# SCH_Nucleo__V5_2022-11-29.net
KiCad netlist of a schematic drawn in EasyEDA
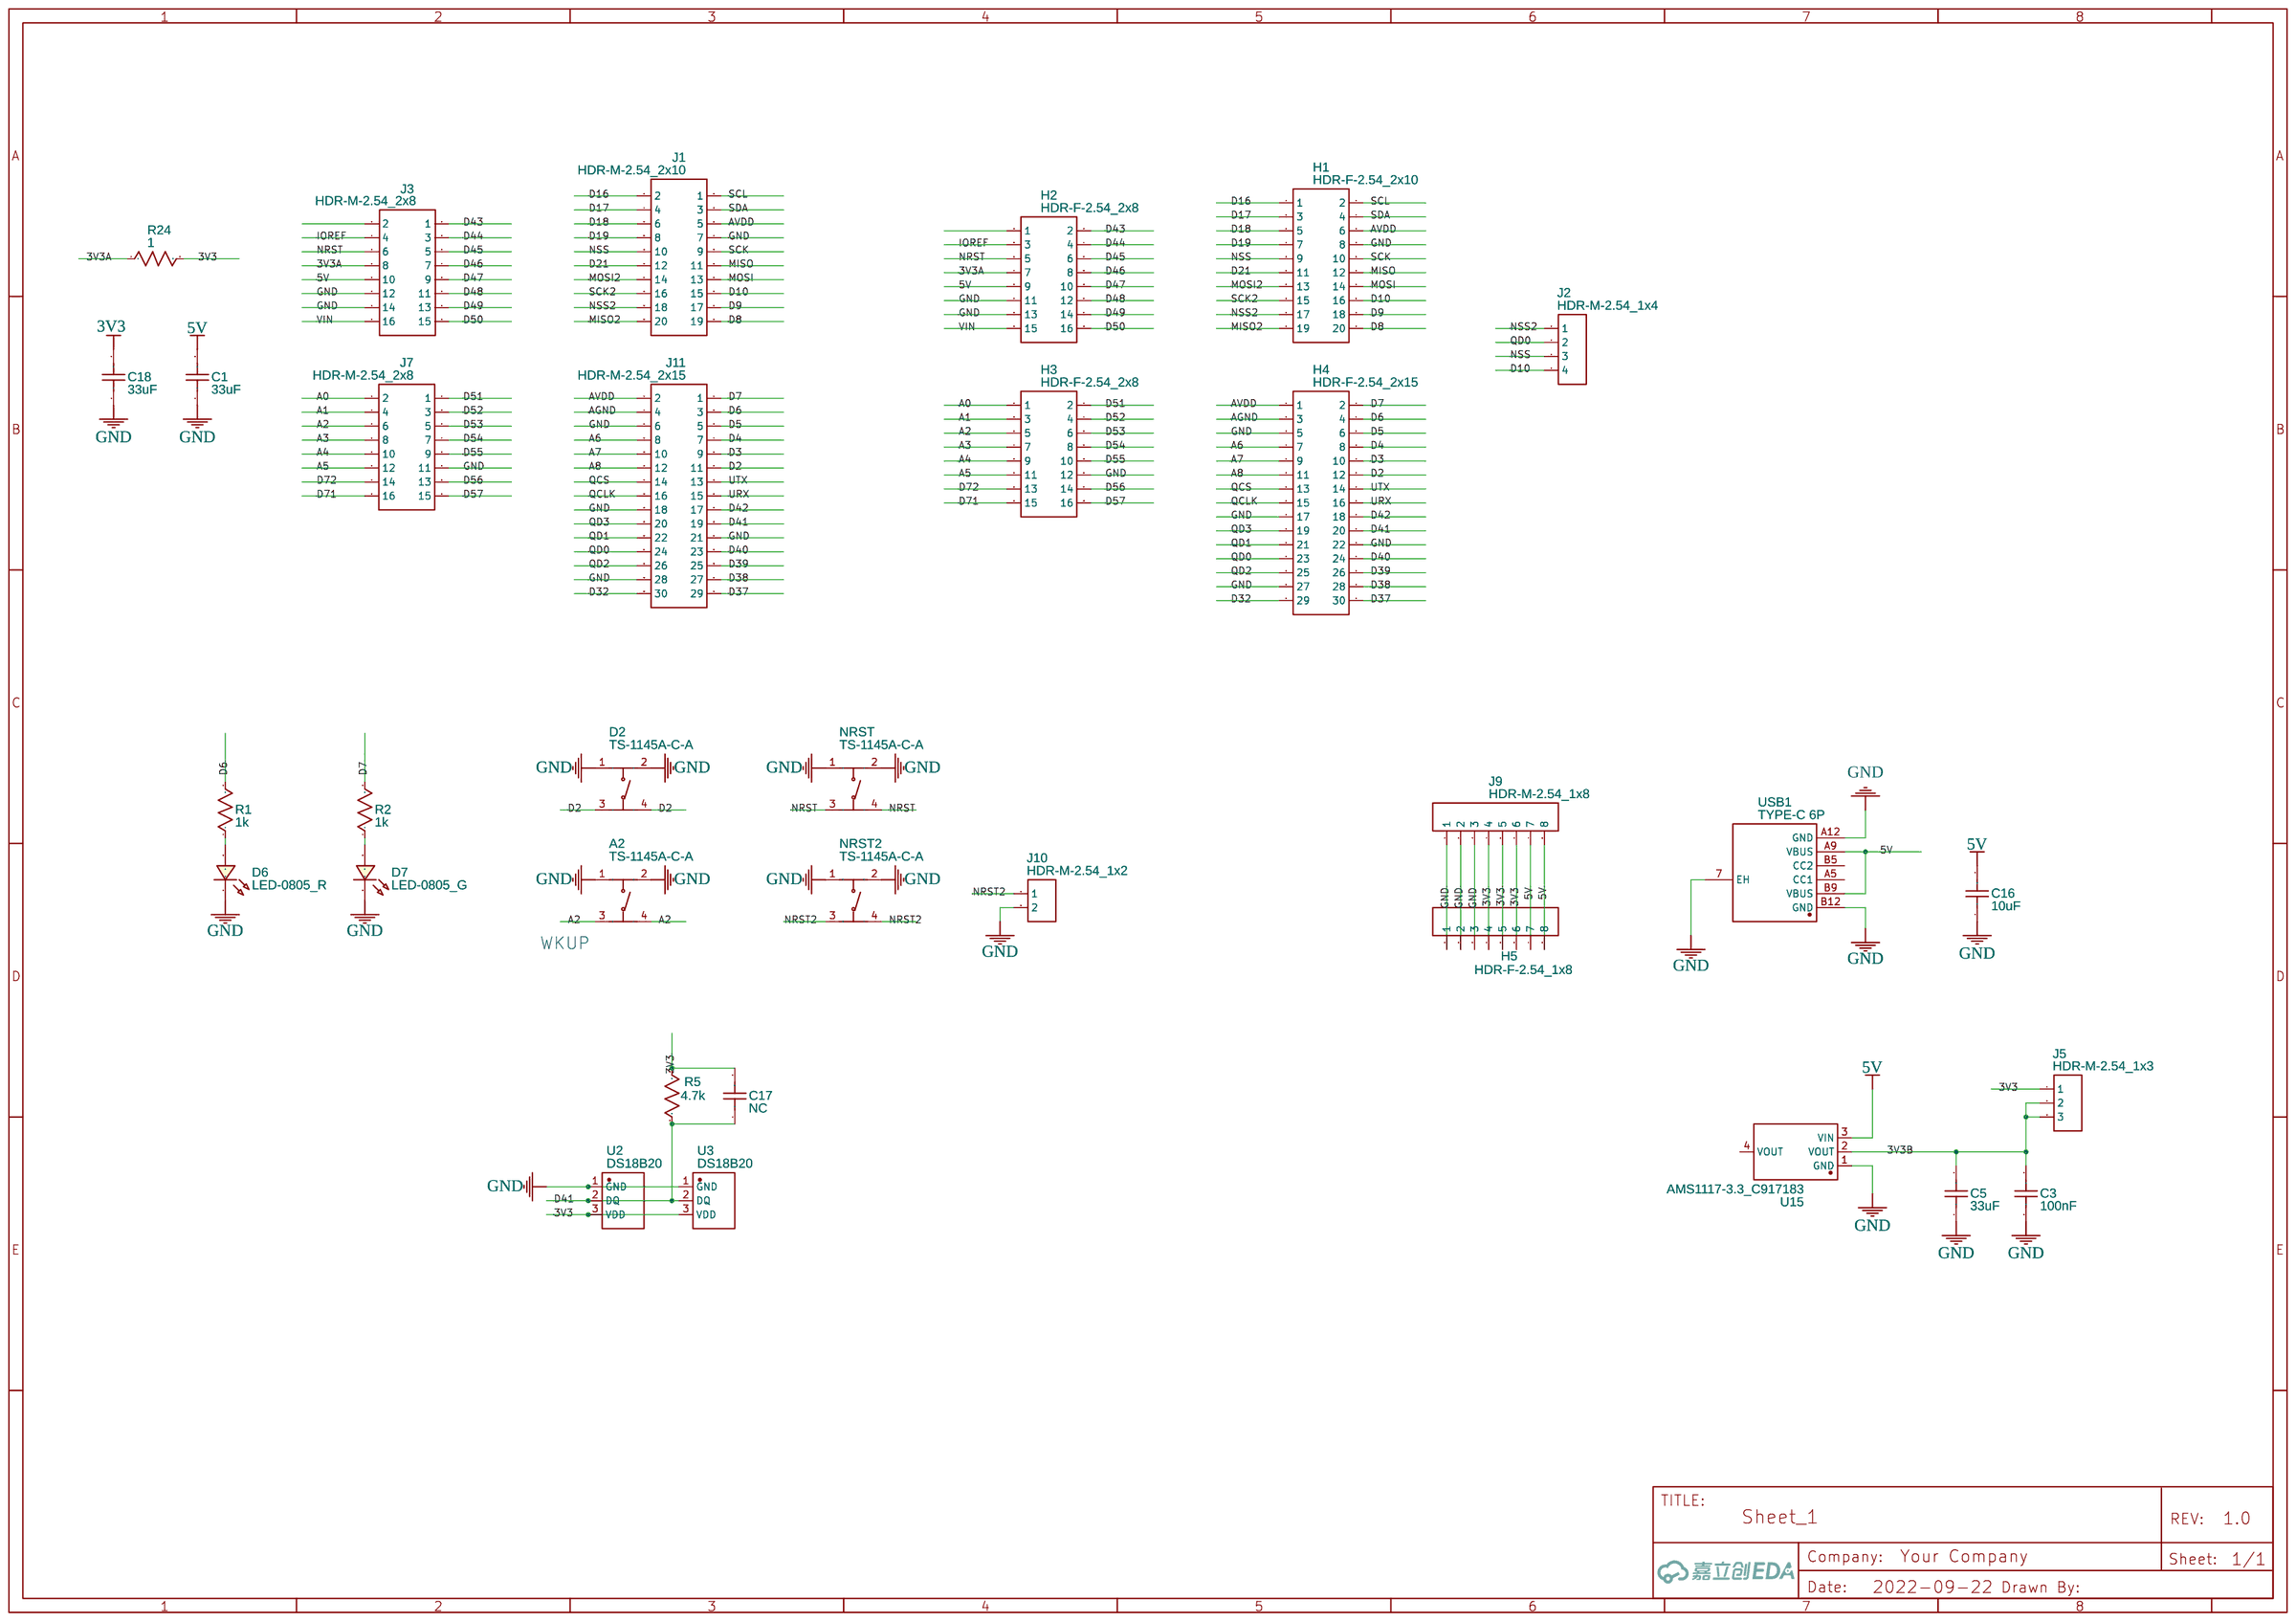
[diagram p0: 连接器]
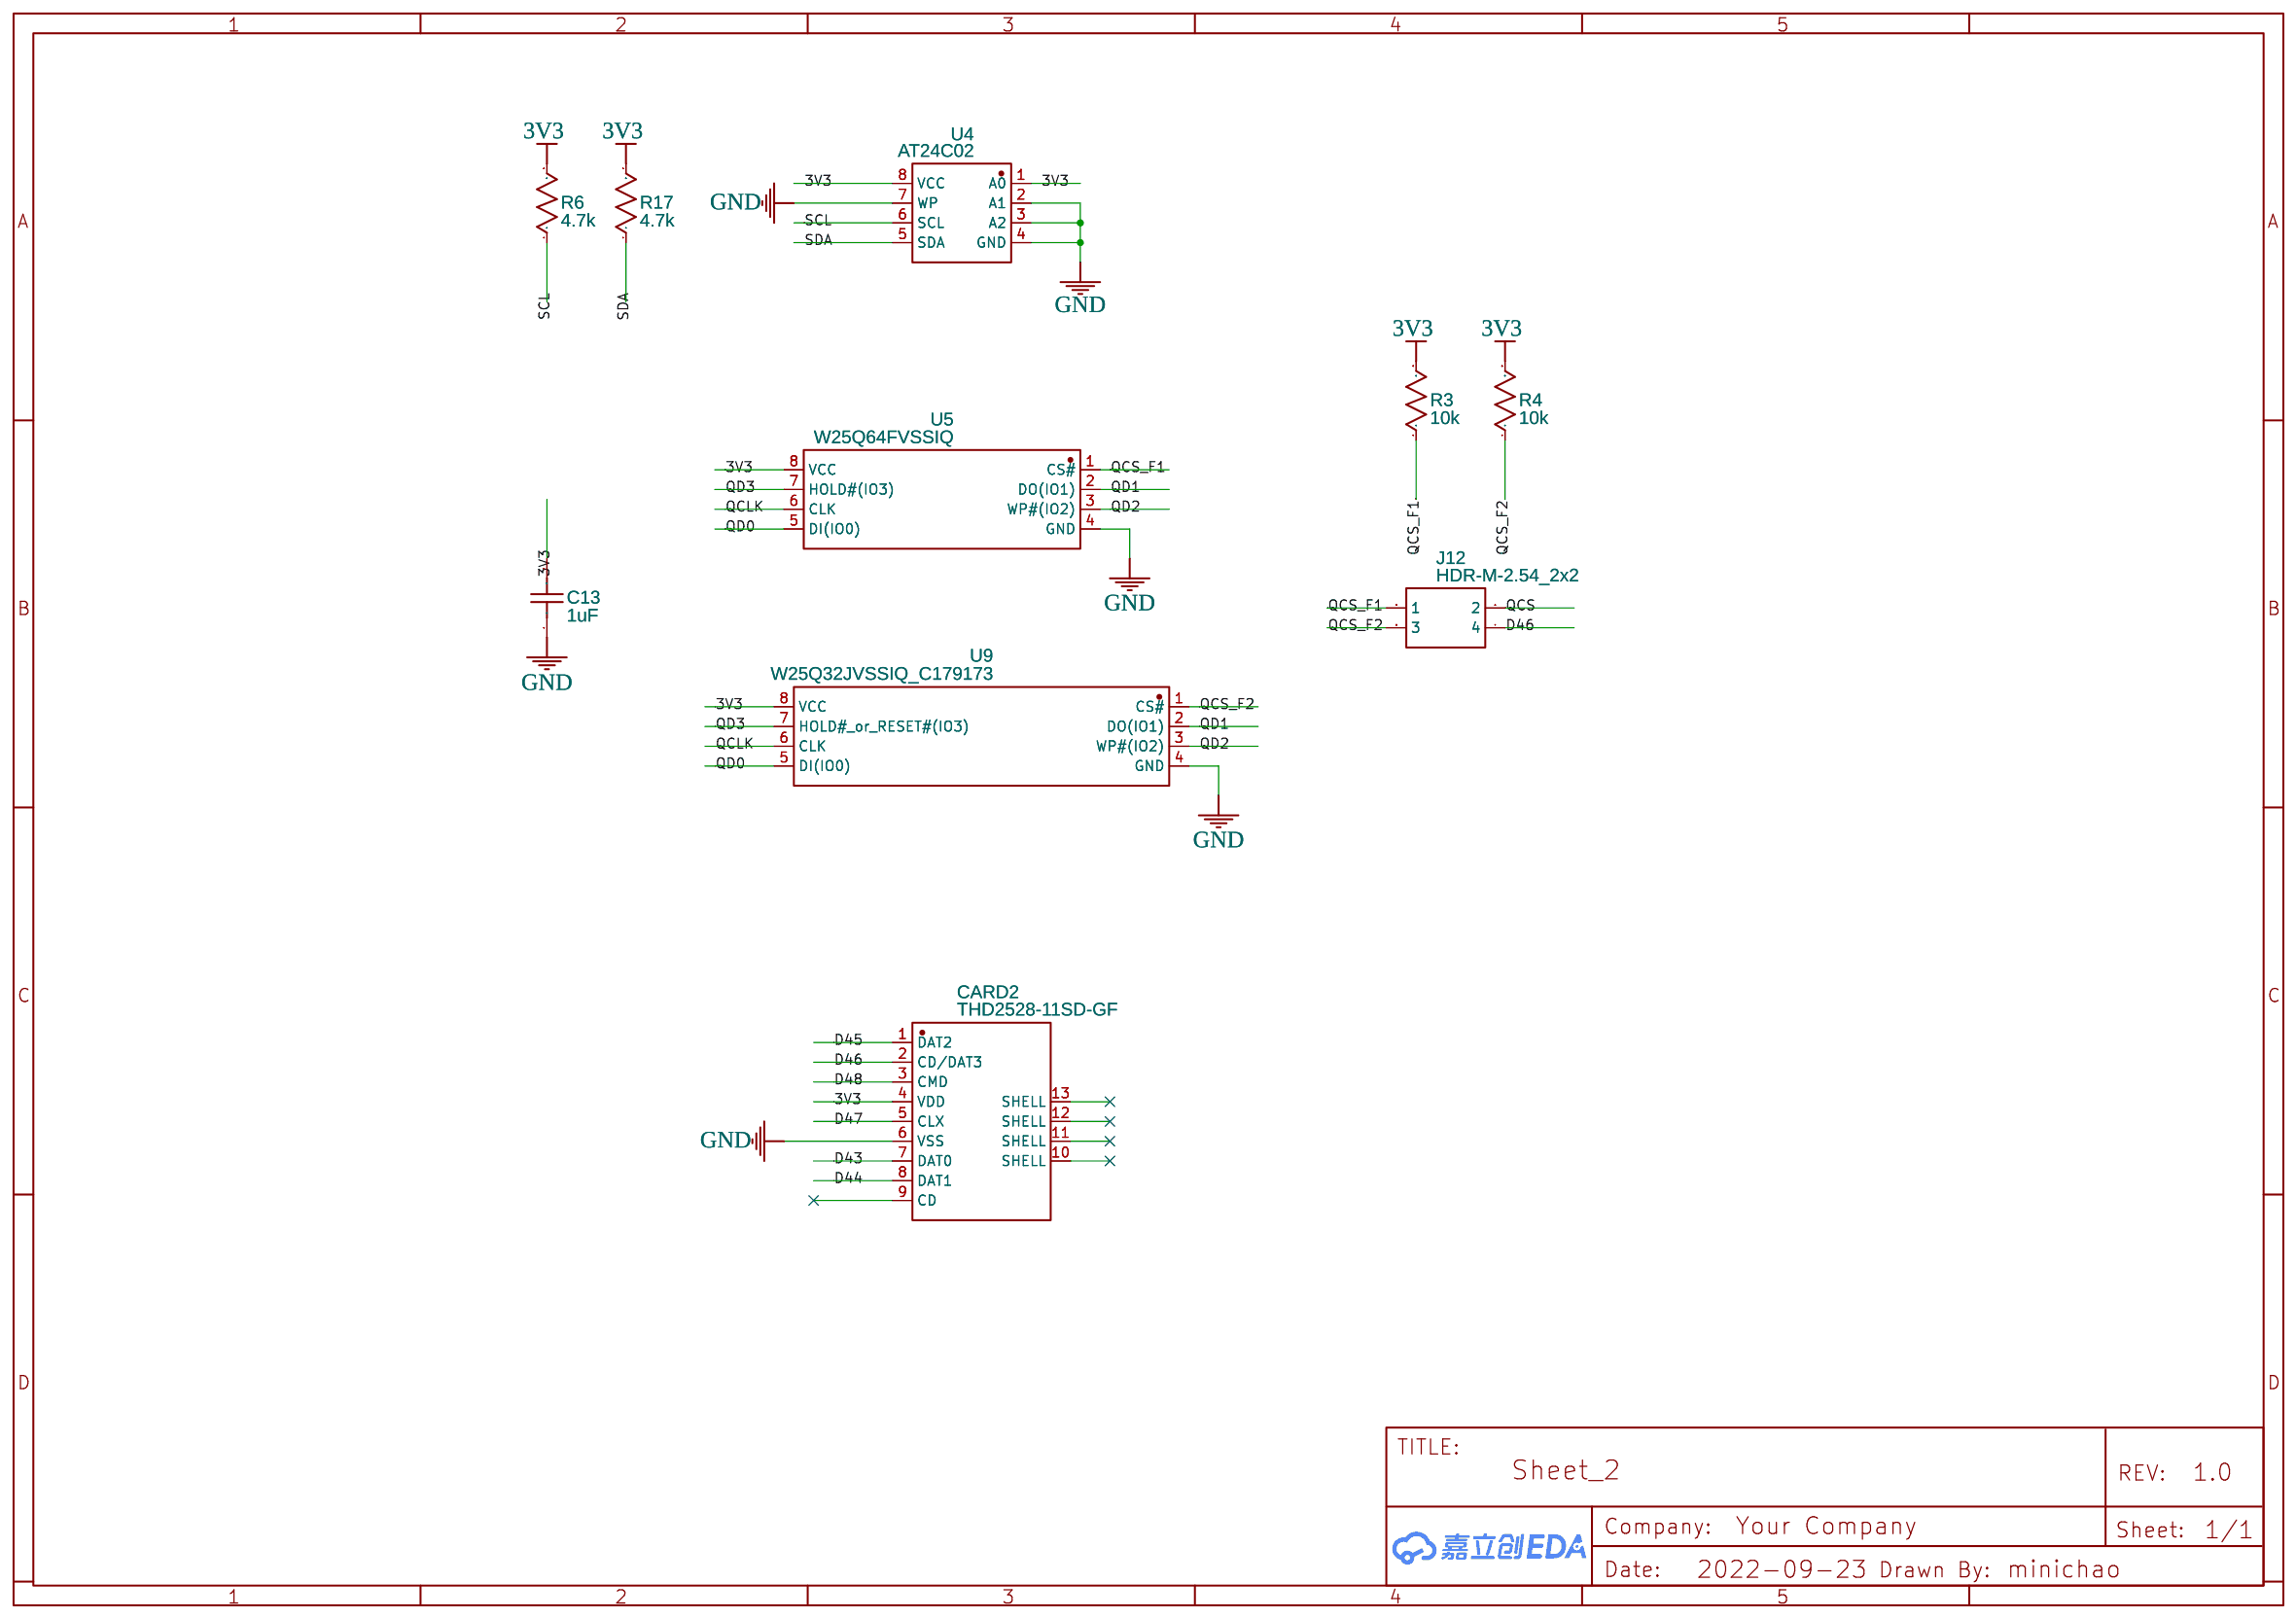
[diagram p1: 存储]
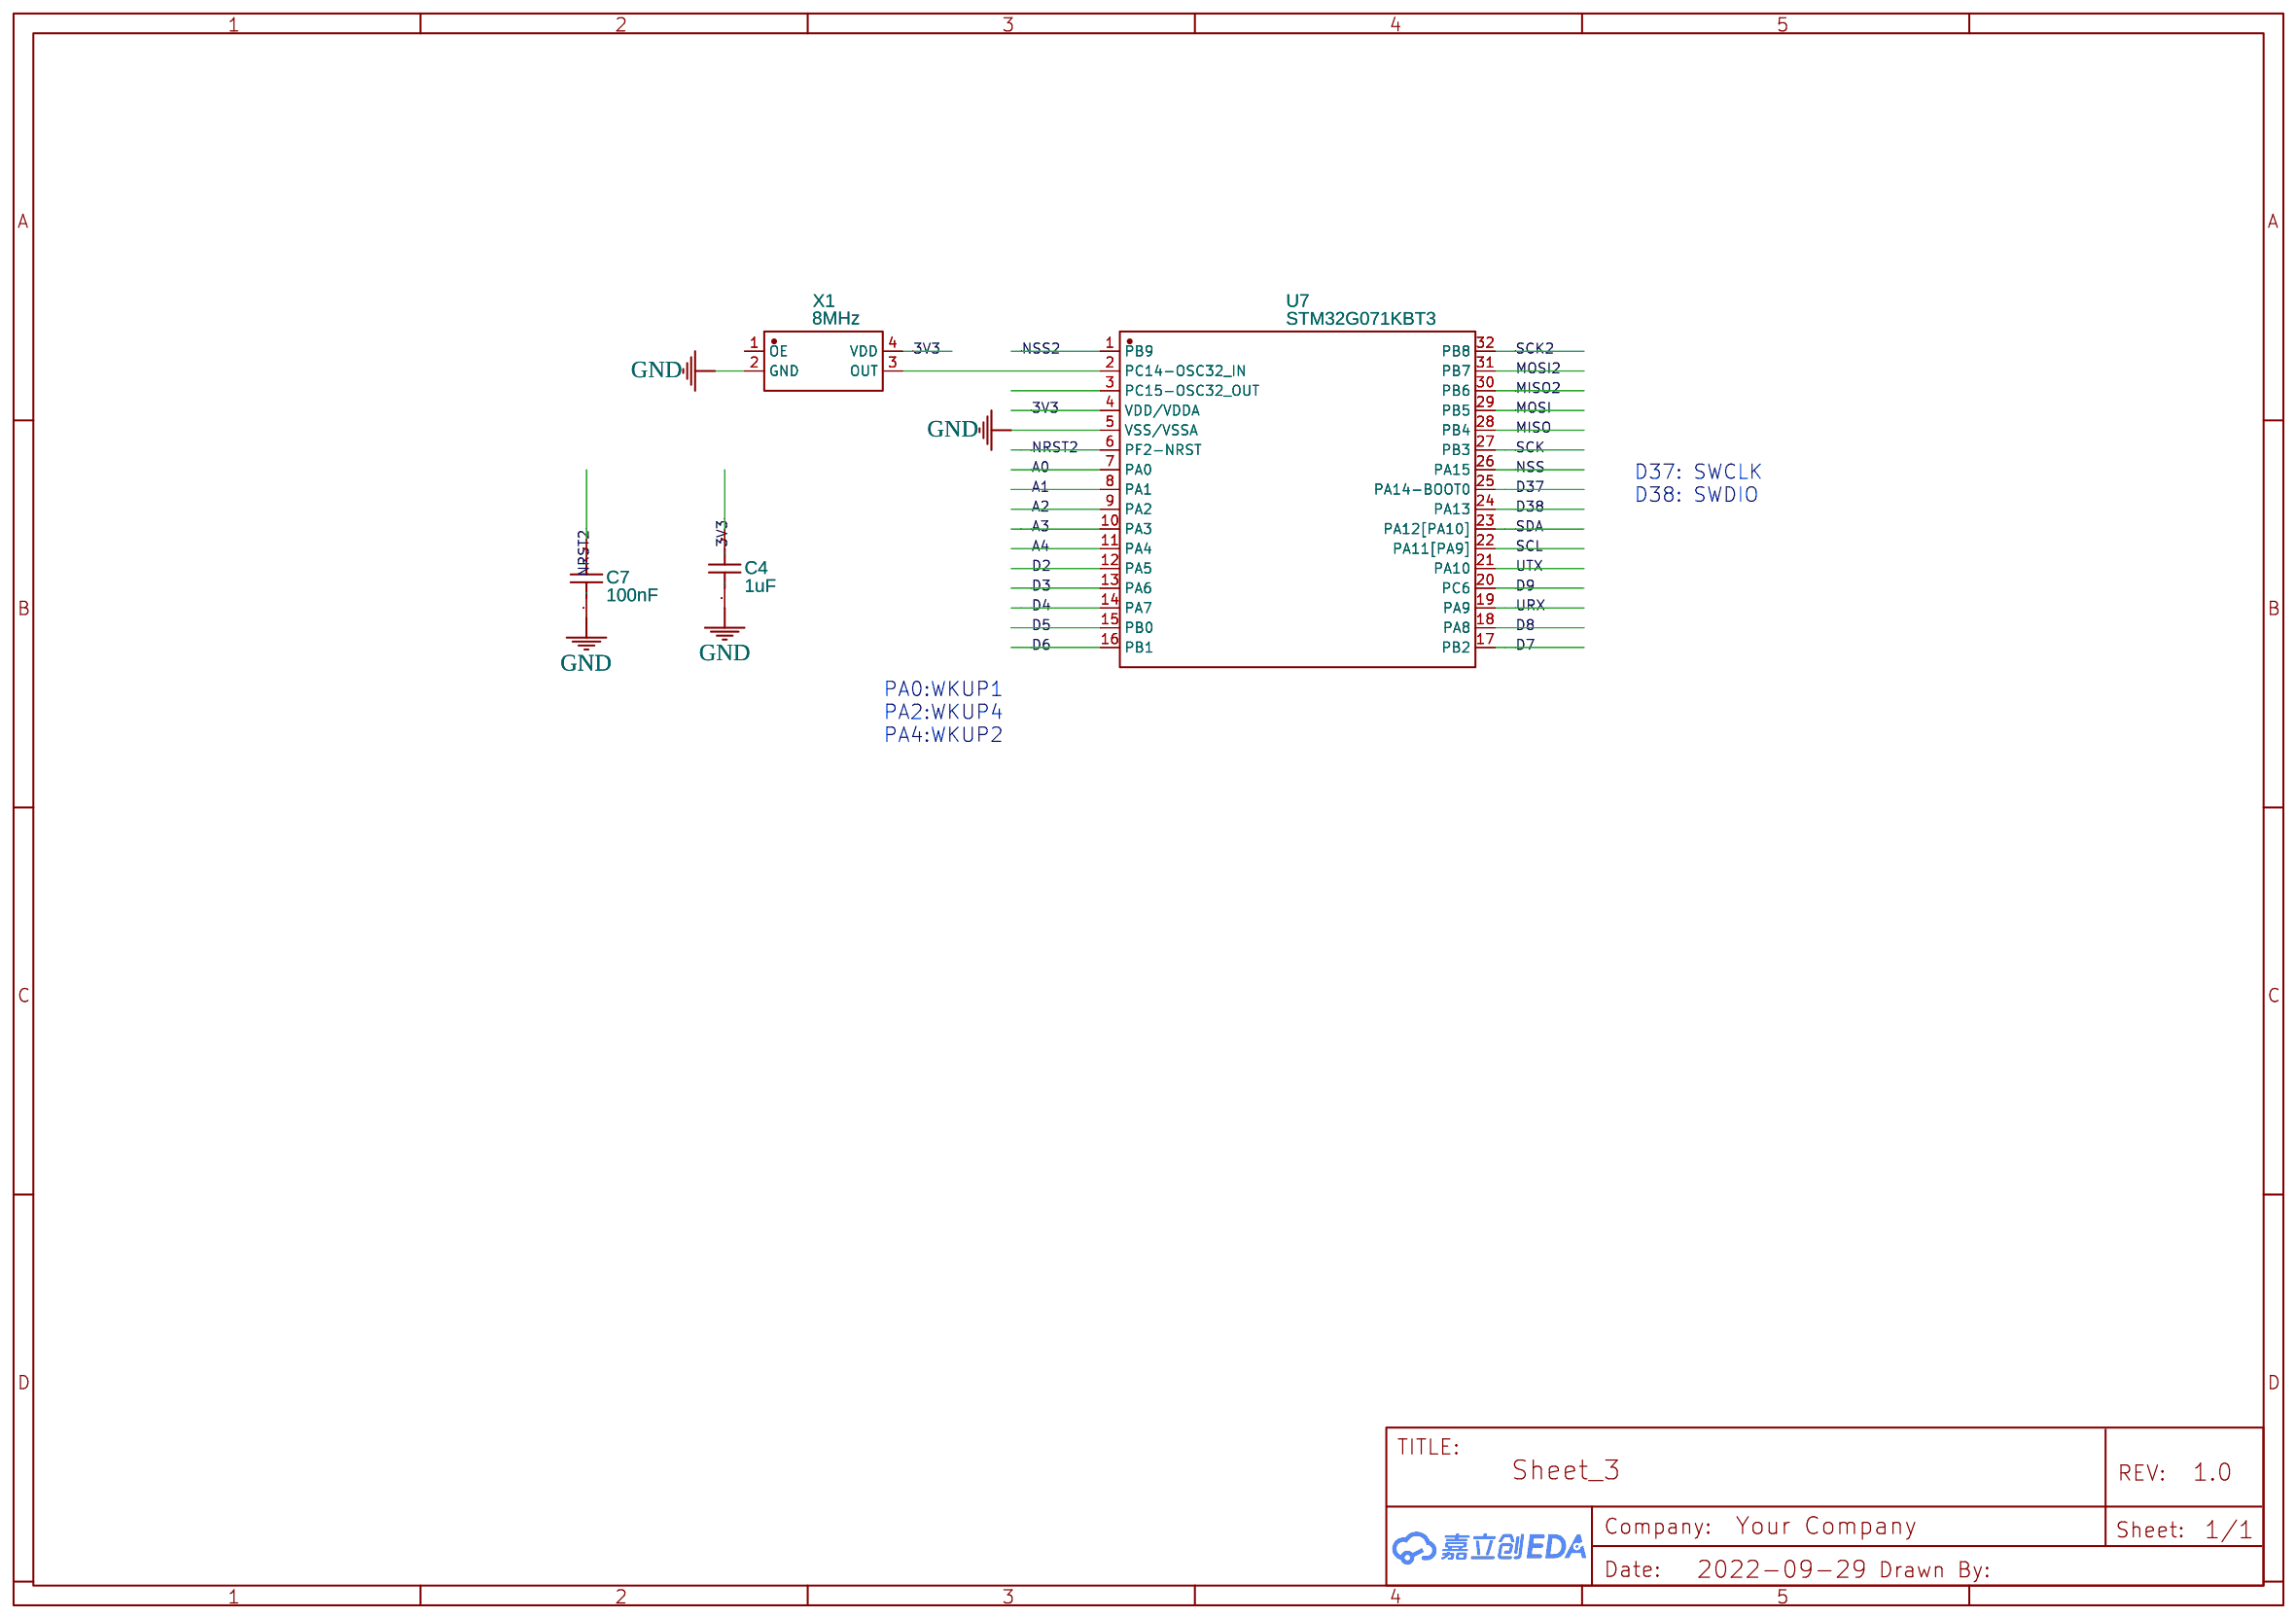
[diagram p2: mcu]
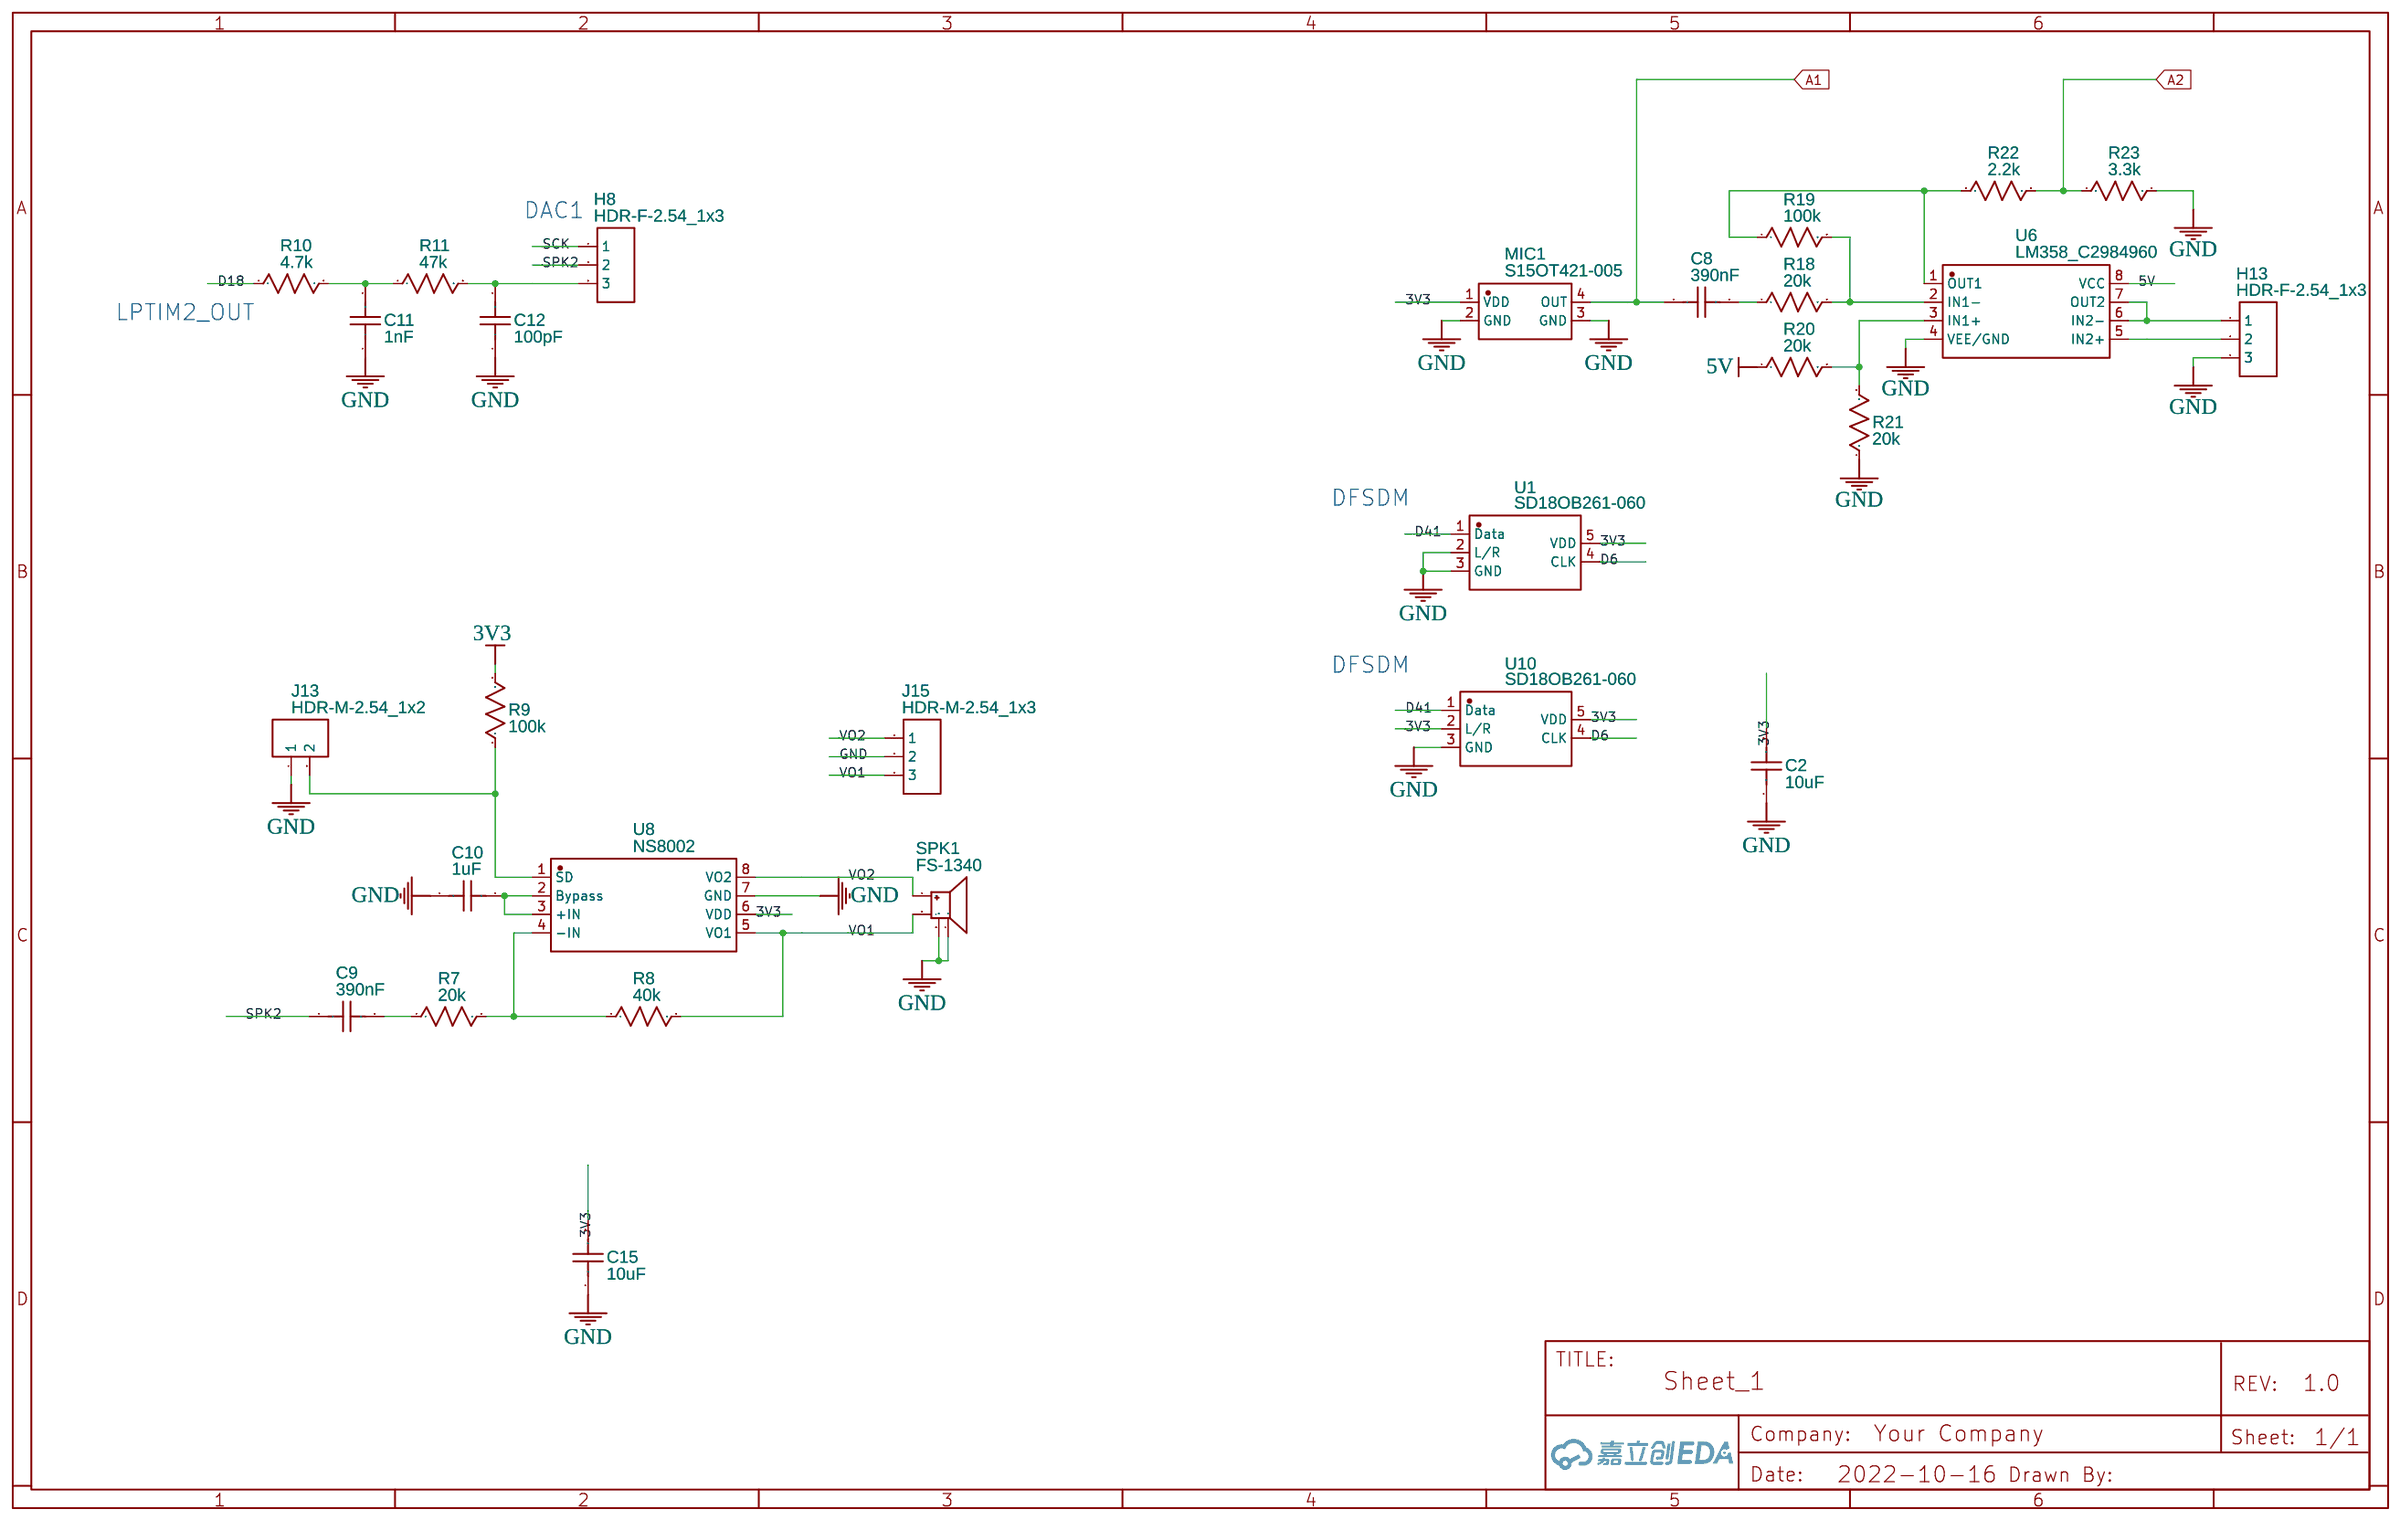
[diagram p3: 音频]
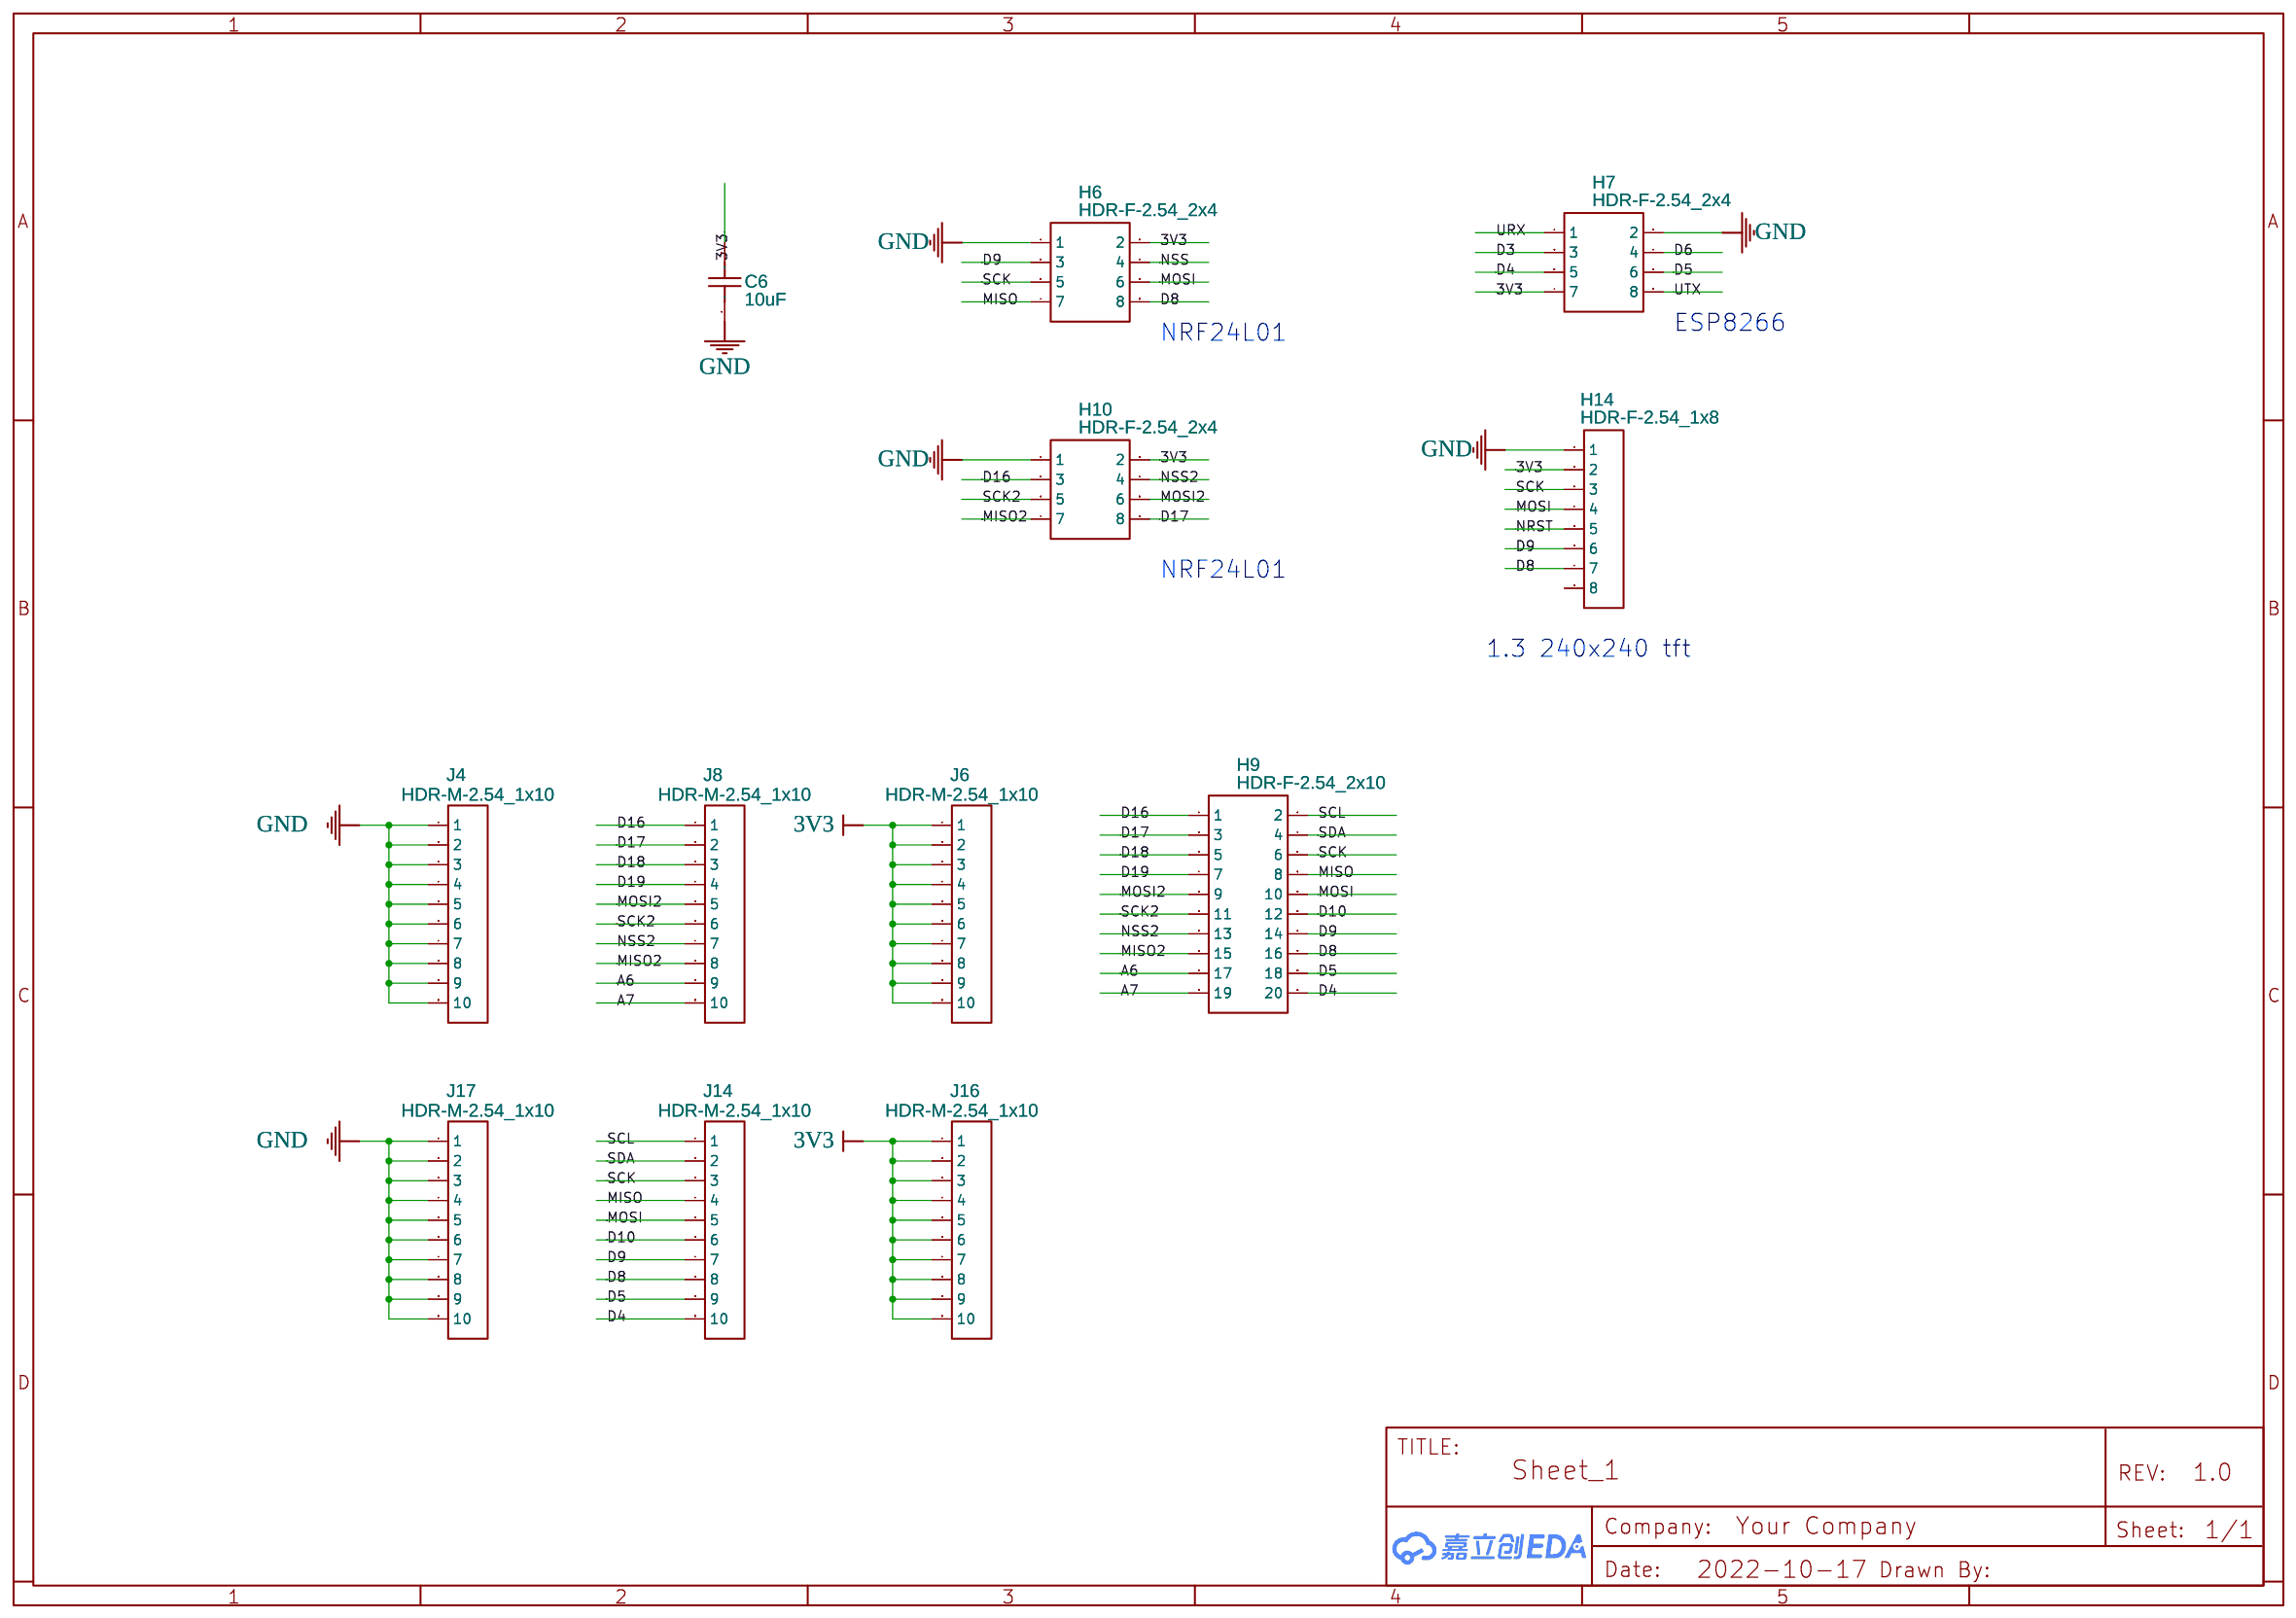
[diagram p4: 无线显示]

(export (version "E")
  (design (tool "Eeschema 10.0.6"))
  (components
    (comp (ref "A2")
      (value "TS-1145A-C-A")
      (fields (field (name "BOM_Supplier Part") "C318903"))
      (libsource (lib "") (part "TS-1145A-C-A_1"))
    )
    (comp (ref "C1")
      (value "33uF")
      (fields
        (field (name "BOM_Manufacturer Part") "C3225X5R0J336MT0A0N")
        (field (name "BOM_Supplier Part") "C695362")
      )
      (libsource (lib "") (part "C3225X5R0J336MT0A0N"))
    )
    (comp (ref "C3") (value "100nF") (libsource (lib "") (part "C_0805_US")))
    (comp (ref "C5")
      (value "33uF")
      (fields
        (field (name "BOM_Manufacturer Part") "C3225X5R0J336MT0A0N")
        (field (name "BOM_Supplier Part") "C695362")
      )
      (libsource (lib "") (part "C3225X5R0J336MT0A0N"))
    )
    (comp (ref "C16")
      (value "10uF")
      (fields
        (field (name "BOM_Manufacturer Part") "0805B105M500NT")
        (field (name "BOM_Supplier Part") "C2913555")
      )
      (libsource (lib "") (part "C_0805_US"))
    )
    (comp (ref "C17") (value "NC") (libsource (lib "") (part "C_0805_US")))
    (comp (ref "C18")
      (value "33uF")
      (fields
        (field (name "BOM_Manufacturer Part") "C3225X5R0J336MT0A0N")
        (field (name "BOM_Supplier Part") "C695362")
      )
      (libsource (lib "") (part "C3225X5R0J336MT0A0N"))
    )
    (comp (ref "D2")
      (value "TS-1145A-C-A")
      (fields (field (name "BOM_Supplier Part") "C318903"))
      (libsource (lib "") (part "TS-1145A-C-A_2"))
    )
    (comp (ref "D6")
      (value "LED-0805_R")
      (fields
        (field (name "BOM_Manufacturer Part") "17-21SURC/S530-A3/TR8")
        (field (name "BOM_Supplier Part") "C72037")
      )
      (libsource (lib "") (part "LED-0805_R"))
    )
    (comp (ref "D7")
      (value "LED-0805_G")
      (fields (field (name "BOM_Manufacturer Part") "NCD0805G1") (field (name "BOM_Supplier Part") "C84260"))
      (libsource (lib "") (part "LED-0805_G"))
    )
    (comp (ref "H1")
      (value "HDR-F-2.54_2x10")
      (fields (field (name "BOM_Supplier Part") "C30867"))
      (libsource (lib "") (part "HDR-F-2.54_2x10"))
    )
    (comp (ref "H2")
      (value "HDR-F-2.54_2x8")
      (fields (field (name "BOM_Supplier Part") "C30734"))
      (libsource (lib "") (part "HDR-F-2.54_2x8"))
    )
    (comp (ref "H3")
      (value "HDR-F-2.54_2x8")
      (fields (field (name "BOM_Supplier Part") "C30734"))
      (libsource (lib "") (part "HDR-F-2.54_2x8"))
    )
    (comp (ref "H4")
      (value "HDR-F-2.54_2x15")
      (fields (field (name "BOM_Supplier Part") "C169818"))
      (libsource (lib "") (part "HDR-F-2.54_2x15"))
    )
    (comp (ref "H5")
      (value "HDR-F-2.54_1x8")
      (fields (field (name "BOM_Supplier Part") "C225505"))
      (libsource (lib "") (part "HDR-F-2.54_1x8"))
    )
    (comp (ref "J1")
      (value "HDR-M-2.54_2x10")
      (fields (field (name "BOM_Supplier Part") "C124359"))
      (libsource (lib "") (part "HDR-M-2.54_2x10"))
    )
    (comp (ref "J2")
      (value "HDR-M-2.54_1x4")
      (fields (field (name "BOM_Supplier Part") "C124378"))
      (libsource (lib "") (part "HDR-M-2.54_1x4"))
    )
    (comp (ref "J3")
      (value "HDR-M-2.54_2x8")
      (fields (field (name "BOM_Supplier Part") "C68234"))
      (libsource (lib "") (part "HDR-M-2.54_2x8"))
    )
    (comp (ref "J5")
      (value "HDR-M-2.54_1x3")
      (fields (field (name "BOM_Supplier Part") "C180248"))
      (libsource (lib "") (part "HDR-M-2.54_1x3"))
    )
    (comp (ref "J7")
      (value "HDR-M-2.54_2x8")
      (fields (field (name "BOM_Supplier Part") "C68234"))
      (libsource (lib "") (part "HDR-M-2.54_2x8_1"))
    )
    (comp (ref "J9")
      (value "HDR-M-2.54_1x8")
      (fields (field (name "BOM_Supplier Part") "C190820"))
      (libsource (lib "") (part "HDR-M-2.54_1x8"))
    )
    (comp (ref "J10")
      (value "HDR-M-2.54_1x2")
      (fields (field (name "BOM_Supplier Part") "C124375"))
      (libsource (lib "") (part "HDR-M-2.54_1x2"))
    )
    (comp (ref "J11")
      (value "HDR-M-2.54_2x15")
      (fields (field (name "BOM_Supplier Part") "C56496"))
      (libsource (lib "") (part "HDR-M-2.54_2x15"))
    )
    (comp (ref "NRST")
      (value "TS-1145A-C-A")
      (fields (field (name "BOM_Supplier Part") "C318903"))
      (libsource (lib "") (part "TS-1145A-C-A"))
    )
    (comp (ref "NRST2")
      (value "TS-1145A-C-A")
      (fields (field (name "BOM_Supplier Part") "C318903"))
      (libsource (lib "") (part "TS-1145A-C-A"))
    )
    (comp (ref "R1")
      (value "1k")
      (fields
        (field (name "BOM_Manufacturer Part") "TC0525F1001T5E")
        (field (name "BOM_Supplier Part") "C75781")
      )
      (libsource (lib "") (part "R_0805_US"))
    )
    (comp (ref "R2")
      (value "1k")
      (fields
        (field (name "BOM_Manufacturer Part") "TC0525F1001T5E")
        (field (name "BOM_Supplier Part") "C75781")
      )
      (libsource (lib "") (part "R_0805_US"))
    )
    (comp (ref "R5") (value "4.7k") (libsource (lib "") (part "R_0805_US")))
    (comp (ref "R24") (value "1") (libsource (lib "") (part "R_0805_US_1")))
    (comp (ref "U2")
      (value "DS18B20")
      (fields (field (name "BOM_Supplier Part") "C376006"))
      (libsource (lib "") (part "DS18B20"))
    )
    (comp (ref "U3")
      (value "DS18B20")
      (fields (field (name "BOM_Supplier Part") "C376006"))
      (libsource (lib "") (part "DS18B20"))
    )
    (comp (ref "U15")
      (value "AMS1117-3.3_C917183")
      (fields
        (field (name "BOM_Manufacturer Part") "AMS1117-3.3")
        (field (name "BOM_Supplier Part") "C917183")
      )
      (libsource (lib "") (part "AMS1117-3.3_C917183"))
    )
    (comp (ref "USB1")
      (value "TYPE-C 6P")
      (fields (field (name "BOM_Supplier Part") "C456012"))
      (libsource (lib "") (part "TYPE-C 6P"))
    )
    (comp (ref "C13")
      (value "1uF")
      (fields
        (field (name "BOM_Manufacturer Part") "0805B105M500NT")
        (field (name "BOM_Supplier Part") "C2913555")
      )
      (libsource (lib "") (part "C_0805_US"))
    )
    (comp (ref "CARD2")
      (value "THD2528-11SD-GF")
      (fields (field (name "BOM_Supplier Part") "C283232"))
      (libsource (lib "") (part "THD2528-11SD-GF"))
    )
    (comp (ref "J12")
      (value "HDR-M-2.54_2x2")
      (fields (field (name "BOM_Supplier Part") "C66690"))
      (libsource (lib "") (part "HDR-M-2.54_2x2"))
    )
    (comp (ref "R3") (value "10k") (libsource (lib "") (part "R_0805_US")))
    (comp (ref "R4") (value "10k") (libsource (lib "") (part "R_0805_US")))
    (comp (ref "R6") (value "4.7k") (libsource (lib "") (part "R_0805_US")))
    (comp (ref "R17") (value "4.7k") (libsource (lib "") (part "R_0805_US")))
    (comp (ref "U4")
      (value "AT24C02")
      (fields (field (name "BOM_Supplier Part") "C688857"))
      (libsource (lib "") (part "AT24C02"))
    )
    (comp (ref "U5")
      (value "W25Q64FVSSIQ")
      (fields (field (name "BOM_Supplier Part") "C2943203"))
      (libsource (lib "") (part "W25Q64FVSSIQ"))
    )
    (comp (ref "U9")
      (value "W25Q32JVSSIQ_C179173")
      (fields
        (field (name "BOM_Manufacturer Part") "W25Q32JVSSIQ")
        (field (name "BOM_Supplier Part") "C179173")
      )
      (libsource (lib "") (part "W25Q32JVSSIQ_C179173"))
    )
    (comp (ref "C4")
      (value "1uF")
      (fields
        (field (name "BOM_Manufacturer Part") "0805B105M500NT")
        (field (name "BOM_Supplier Part") "C2913555")
      )
      (libsource (lib "") (part "C_0805_US"))
    )
    (comp (ref "C7") (value "100nF") (libsource (lib "") (part "C_0805_US")))
    (comp (ref "U7")
      (value "STM32G071KBT3")
      (fields (field (name "BOM_Supplier Part") "C724238"))
      (libsource (lib "") (part "STM32G071KBT3"))
    )
    (comp (ref "X1")
      (value "8MHz")
      (fields
        (field (name "BOM_Manufacturer Part") "S2H008000I3CHE-T")
        (field (name "BOM_Supplier Part") "C253908")
      )
      (libsource (lib "") (part "S2H008000I3CHE-T"))
    )
    (comp (ref "C2")
      (value "10uF")
      (fields
        (field (name "BOM_Manufacturer Part") "0805B105M500NT")
        (field (name "BOM_Supplier Part") "C2913555")
      )
      (libsource (lib "") (part "C_0805_US"))
    )
    (comp (ref "C8") (value "390nF") (libsource (lib "") (part "C_0805_US_1")))
    (comp (ref "C9") (value "390nF") (libsource (lib "") (part "C_0805_US_1")))
    (comp (ref "C10") (value "1uF") (libsource (lib "") (part "C_0805_US_2")))
    (comp (ref "C11") (value "1nF") (libsource (lib "") (part "C_0805_US")))
    (comp (ref "C12") (value "100pF") (libsource (lib "") (part "C_0805_US")))
    (comp (ref "C15")
      (value "10uF")
      (fields
        (field (name "BOM_Manufacturer Part") "0805B105M500NT")
        (field (name "BOM_Supplier Part") "C2913555")
      )
      (libsource (lib "") (part "C_0805_US"))
    )
    (comp (ref "H8")
      (value "HDR-F-2.54_1x3")
      (fields (field (name "BOM_Supplier Part") "C146690"))
      (libsource (lib "") (part "HDR-F-2.54_1x3"))
    )
    (comp (ref "H13")
      (value "HDR-F-2.54_1x3")
      (fields (field (name "BOM_Supplier Part") "C146690"))
      (libsource (lib "") (part "HDR-F-2.54_1x3"))
    )
    (comp (ref "J13")
      (value "HDR-M-2.54_1x2")
      (fields (field (name "BOM_Supplier Part") "C124375"))
      (libsource (lib "") (part "HDR-M-2.54_1x2"))
    )
    (comp (ref "J15")
      (value "HDR-M-2.54_1x3")
      (fields (field (name "BOM_Supplier Part") "C180248"))
      (libsource (lib "") (part "HDR-M-2.54_1x3"))
    )
    (comp (ref "MIC1")
      (value "S15OT421-005")
      (fields (field (name "BOM_Supplier Part") "C2684419"))
      (libsource (lib "") (part "S15OT421-005"))
    )
    (comp (ref "R7") (value "20k") (libsource (lib "") (part "R_0805_US")))
    (comp (ref "R8") (value "40k") (libsource (lib "") (part "R_0805_US")))
    (comp (ref "R9") (value "100k") (libsource (lib "") (part "R_0805_US_1")))
    (comp (ref "R10") (value "4.7k") (libsource (lib "") (part "R_0805_US")))
    (comp (ref "R11") (value "47k") (libsource (lib "") (part "R_0805_US")))
    (comp (ref "R18") (value "20k") (libsource (lib "") (part "R_0805_US")))
    (comp (ref "R19") (value "100k") (libsource (lib "") (part "R_0805_US")))
    (comp (ref "R20") (value "20k") (libsource (lib "") (part "R_0805_US")))
    (comp (ref "R21") (value "20k") (libsource (lib "") (part "R_0805_US_1")))
    (comp (ref "R22") (value "2.2k") (libsource (lib "") (part "R_0805_US")))
    (comp (ref "R23") (value "3.3k") (libsource (lib "") (part "R_0805_US")))
    (comp (ref "SPK1")
      (value "FS-1340")
      (fields (field (name "BOM_Supplier Part") "C482342"))
      (libsource (lib "") (part "FS-1340"))
    )
    (comp (ref "U1")
      (value "SD18OB261-060")
      (fields (field (name "BOM_Supplier Part") "C2895290"))
      (libsource (lib "") (part "SD18OB261-060"))
    )
    (comp (ref "U6")
      (value "LM358_C2984960")
      (fields (field (name "BOM_Manufacturer Part") "LM358") (field (name "BOM_Supplier Part") "C2984960"))
      (libsource (lib "") (part "LM358_C2984960"))
    )
    (comp (ref "U8")
      (value "NS8002")
      (fields (field (name "BOM_Supplier Part") "C189960"))
      (libsource (lib "") (part "NS8002"))
    )
    (comp (ref "U10")
      (value "SD18OB261-060")
      (fields (field (name "BOM_Supplier Part") "C2895290"))
      (libsource (lib "") (part "SD18OB261-060"))
    )
    (comp (ref "C6")
      (value "10uF")
      (fields
        (field (name "BOM_Manufacturer Part") "0805B105M500NT")
        (field (name "BOM_Supplier Part") "C2913555")
      )
      (libsource (lib "") (part "C_0805_US"))
    )
    (comp (ref "H6")
      (value "HDR-F-2.54_2x4")
      (fields (field (name "BOM_Supplier Part") "C239344"))
      (libsource (lib "") (part "HDR-F-2.54_2x4"))
    )
    (comp (ref "H7")
      (value "HDR-F-2.54_2x4")
      (fields (field (name "BOM_Supplier Part") "C239344"))
      (libsource (lib "") (part "HDR-F-2.54_2x4"))
    )
    (comp (ref "H9")
      (value "HDR-F-2.54_2x10")
      (fields (field (name "BOM_Supplier Part") "C30867"))
      (libsource (lib "") (part "HDR-F-2.54_2x10"))
    )
    (comp (ref "H10")
      (value "HDR-F-2.54_2x4")
      (fields (field (name "BOM_Supplier Part") "C239344"))
      (libsource (lib "") (part "HDR-F-2.54_2x4"))
    )
    (comp (ref "H14")
      (value "HDR-F-2.54_1x8")
      (fields (field (name "BOM_Supplier Part") "C225505"))
      (libsource (lib "") (part "HDR-F-2.54_1x8"))
    )
    (comp (ref "J4")
      (value "HDR-M-2.54_1x10")
      (fields (field (name "BOM_Supplier Part") "C57369"))
      (libsource (lib "") (part "HDR-M-2.54_1x10"))
    )
    (comp (ref "J6")
      (value "HDR-M-2.54_1x10")
      (fields (field (name "BOM_Supplier Part") "C57369"))
      (libsource (lib "") (part "HDR-M-2.54_1x10"))
    )
    (comp (ref "J8")
      (value "HDR-M-2.54_1x10")
      (fields (field (name "BOM_Supplier Part") "C57369"))
      (libsource (lib "") (part "HDR-M-2.54_1x10"))
    )
    (comp (ref "J14")
      (value "HDR-M-2.54_1x10")
      (fields (field (name "BOM_Supplier Part") "C57369"))
      (libsource (lib "") (part "HDR-M-2.54_1x10"))
    )
    (comp (ref "J16")
      (value "HDR-M-2.54_1x10")
      (fields (field (name "BOM_Supplier Part") "C57369"))
      (libsource (lib "") (part "HDR-M-2.54_1x10"))
    )
    (comp (ref "J17")
      (value "HDR-M-2.54_1x10")
      (fields (field (name "BOM_Supplier Part") "C57369"))
      (libsource (lib "") (part "HDR-M-2.54_1x10"))
    )
  )
  (nets
    (net (code "1") (name "3V3") (class "Default")
      (node (ref "C13") (pin "2") (pinfunction "2_2") (pintype "unspecified"))
      (node (ref "C15") (pin "2") (pinfunction "2_2") (pintype "unspecified"))
      (node (ref "C17") (pin "2") (pinfunction "2_2") (pintype "unspecified"))
      (node (ref "C18") (pin "2") (pinfunction "2_2") (pintype "unspecified"))
      (node (ref "C2") (pin "2") (pinfunction "2_2") (pintype "unspecified"))
      (node (ref "C4") (pin "2") (pinfunction "2_2") (pintype "unspecified"))
      (node (ref "C6") (pin "2") (pinfunction "2_2") (pintype "unspecified"))
      (node (ref "CARD2") (pin "4") (pinfunction "VDD_4") (pintype "unspecified"))
      (node (ref "H10") (pin "2") (pinfunction "2_2") (pintype "unspecified"))
      (node (ref "H14") (pin "2") (pinfunction "2_2") (pintype "unspecified"))
      (node (ref "H5") (pin "4") (pinfunction "4_4") (pintype "unspecified"))
      (node (ref "H5") (pin "5") (pinfunction "5_5") (pintype "unspecified"))
      (node (ref "H5") (pin "6") (pinfunction "6_6") (pintype "unspecified"))
      (node (ref "H6") (pin "2") (pinfunction "2_2") (pintype "unspecified"))
      (node (ref "H7") (pin "7") (pinfunction "7_7") (pintype "unspecified"))
      (node (ref "J16") (pin "1") (pinfunction "1_1") (pintype "unspecified"))
      (node (ref "J16") (pin "10") (pinfunction "10_10") (pintype "unspecified"))
      (node (ref "J16") (pin "2") (pinfunction "2_2") (pintype "unspecified"))
      (node (ref "J16") (pin "3") (pinfunction "3_3") (pintype "unspecified"))
      (node (ref "J16") (pin "4") (pinfunction "4_4") (pintype "unspecified"))
      (node (ref "J16") (pin "5") (pinfunction "5_5") (pintype "unspecified"))
      (node (ref "J16") (pin "6") (pinfunction "6_6") (pintype "unspecified"))
      (node (ref "J16") (pin "7") (pinfunction "7_7") (pintype "unspecified"))
      (node (ref "J16") (pin "8") (pinfunction "8_8") (pintype "unspecified"))
      (node (ref "J16") (pin "9") (pinfunction "9_9") (pintype "unspecified"))
      (node (ref "J5") (pin "1") (pinfunction "1_1") (pintype "input"))
      (node (ref "J6") (pin "1") (pinfunction "1_1") (pintype "unspecified"))
      (node (ref "J6") (pin "10") (pinfunction "10_10") (pintype "unspecified"))
      (node (ref "J6") (pin "2") (pinfunction "2_2") (pintype "unspecified"))
      (node (ref "J6") (pin "3") (pinfunction "3_3") (pintype "unspecified"))
      (node (ref "J6") (pin "4") (pinfunction "4_4") (pintype "unspecified"))
      (node (ref "J6") (pin "5") (pinfunction "5_5") (pintype "unspecified"))
      (node (ref "J6") (pin "6") (pinfunction "6_6") (pintype "unspecified"))
      (node (ref "J6") (pin "7") (pinfunction "7_7") (pintype "unspecified"))
      (node (ref "J6") (pin "8") (pinfunction "8_8") (pintype "unspecified"))
      (node (ref "J6") (pin "9") (pinfunction "9_9") (pintype "unspecified"))
      (node (ref "J9") (pin "4") (pinfunction "4_4") (pintype "unspecified"))
      (node (ref "J9") (pin "5") (pinfunction "5_5") (pintype "unspecified"))
      (node (ref "J9") (pin "6") (pinfunction "6_6") (pintype "unspecified"))
      (node (ref "MIC1") (pin "1") (pinfunction "VDD_1") (pintype "unspecified"))
      (node (ref "R17") (pin "2") (pinfunction "2_2") (pintype "unspecified"))
      (node (ref "R24") (pin "2") (pinfunction "2_2") (pintype "unspecified"))
      (node (ref "R3") (pin "2") (pinfunction "2_2") (pintype "unspecified"))
      (node (ref "R4") (pin "2") (pinfunction "2_2") (pintype "unspecified"))
      (node (ref "R5") (pin "2") (pinfunction "2_2") (pintype "unspecified"))
      (node (ref "R6") (pin "2") (pinfunction "2_2") (pintype "unspecified"))
      (node (ref "R9") (pin "2") (pinfunction "2_2") (pintype "unspecified"))
      (node (ref "U1") (pin "5") (pinfunction "VDD_5") (pintype "unspecified"))
      (node (ref "U10") (pin "2") (pinfunction "L/R_2") (pintype "unspecified"))
      (node (ref "U10") (pin "5") (pinfunction "VDD_5") (pintype "unspecified"))
      (node (ref "U2") (pin "3") (pinfunction "VDD_3") (pintype "unspecified"))
      (node (ref "U3") (pin "3") (pinfunction "VDD_3") (pintype "unspecified"))
      (node (ref "U4") (pin "1") (pinfunction "A0_1") (pintype "unspecified"))
      (node (ref "U4") (pin "8") (pinfunction "VCC_8") (pintype "unspecified"))
      (node (ref "U5") (pin "8") (pinfunction "VCC_8") (pintype "unspecified"))
      (node (ref "U7") (pin "4") (pinfunction "VDD/VDDA_4") (pintype "unspecified"))
      (node (ref "U8") (pin "6") (pinfunction "VDD_6") (pintype "unspecified"))
      (node (ref "U9") (pin "8") (pinfunction "VCC_8") (pintype "unspecified"))
      (node (ref "X1") (pin "4") (pinfunction "VDD_4") (pintype "unspecified"))
    )
    (net (code "2") (name "3V3A") (class "Default")
      (node (ref "H2") (pin "7") (pinfunction "7_7") (pintype "input"))
      (node (ref "J3") (pin "8") (pinfunction "8_8") (pintype "input"))
      (node (ref "R24") (pin "1") (pinfunction "1_1") (pintype "unspecified"))
    )
    (net (code "3") (name "3V3B") (class "Default")
      (node (ref "C3") (pin "2") (pinfunction "2_2") (pintype "unspecified"))
      (node (ref "C5") (pin "2") (pinfunction "2_2") (pintype "unspecified"))
      (node (ref "J5") (pin "2") (pinfunction "2_2") (pintype "input"))
      (node (ref "J5") (pin "3") (pinfunction "3_3") (pintype "input"))
      (node (ref "U15") (pin "2") (pinfunction "VOUT_2") (pintype "unspecified"))
    )
    (net (code "4") (name "5V") (class "Default")
      (node (ref "C1") (pin "2") (pinfunction "2_2") (pintype "unspecified"))
      (node (ref "C16") (pin "2") (pinfunction "2_2") (pintype "unspecified"))
      (node (ref "H2") (pin "9") (pinfunction "9_9") (pintype "input"))
      (node (ref "H5") (pin "7") (pinfunction "7_7") (pintype "unspecified"))
      (node (ref "H5") (pin "8") (pinfunction "8_8") (pintype "unspecified"))
      (node (ref "J3") (pin "10") (pinfunction "10_10") (pintype "input"))
      (node (ref "J9") (pin "7") (pinfunction "7_7") (pintype "unspecified"))
      (node (ref "J9") (pin "8") (pinfunction "8_8") (pintype "unspecified"))
      (node (ref "R20") (pin "1") (pinfunction "1_1") (pintype "unspecified"))
      (node (ref "U15") (pin "3") (pinfunction "VIN_3") (pintype "unspecified"))
      (node (ref "U6") (pin "8") (pinfunction "VCC_8") (pintype "unspecified"))
      (node (ref "USB1") (pin "A9") (pinfunction "VBUS_A9") (pintype "unspecified"))
      (node (ref "USB1") (pin "B9") (pinfunction "VBUS_B9") (pintype "unspecified"))
    )
    (net (code "5") (name "A0") (class "Default")
      (node (ref "H3") (pin "1") (pinfunction "1_1") (pintype "input"))
      (node (ref "J7") (pin "2") (pinfunction "2_2") (pintype "input"))
      (node (ref "U7") (pin "7") (pinfunction "PA0_7") (pintype "unspecified"))
    )
    (net (code "6") (name "A1") (class "Default")
      (node (ref "C8") (pin "1") (pinfunction "1_1") (pintype "unspecified"))
      (node (ref "H3") (pin "3") (pinfunction "3_3") (pintype "input"))
      (node (ref "J7") (pin "4") (pinfunction "4_4") (pintype "input"))
      (node (ref "MIC1") (pin "4") (pinfunction "OUT_4") (pintype "unspecified"))
      (node (ref "U7") (pin "8") (pinfunction "PA1_8") (pintype "unspecified"))
    )
    (net (code "7") (name "A2") (class "Default")
      (node (ref "A2") (pin "3") (pinfunction "3_3") (pintype "unspecified"))
      (node (ref "A2") (pin "4") (pinfunction "4_4") (pintype "unspecified"))
      (node (ref "H3") (pin "5") (pinfunction "5_5") (pintype "input"))
      (node (ref "J7") (pin "6") (pinfunction "6_6") (pintype "input"))
      (node (ref "R22") (pin "2") (pinfunction "2_2") (pintype "unspecified"))
      (node (ref "R23") (pin "1") (pinfunction "1_1") (pintype "unspecified"))
      (node (ref "U7") (pin "9") (pinfunction "PA2_9") (pintype "unspecified"))
    )
    (net (code "8") (name "A3") (class "Default")
      (node (ref "H3") (pin "7") (pinfunction "7_7") (pintype "input"))
      (node (ref "J7") (pin "8") (pinfunction "8_8") (pintype "input"))
      (node (ref "U7") (pin "10") (pinfunction "PA3_10") (pintype "unspecified"))
    )
    (net (code "9") (name "A4") (class "Default")
      (node (ref "H3") (pin "9") (pinfunction "9_9") (pintype "input"))
      (node (ref "J7") (pin "10") (pinfunction "10_10") (pintype "input"))
      (node (ref "U7") (pin "11") (pinfunction "PA4_11") (pintype "unspecified"))
    )
    (net (code "10") (name "A5") (class "Default")
      (node (ref "H3") (pin "11") (pinfunction "11_11") (pintype "input"))
      (node (ref "J7") (pin "12") (pinfunction "12_12") (pintype "input"))
    )
    (net (code "11") (name "A6") (class "Default")
      (node (ref "H4") (pin "7") (pinfunction "7_7") (pintype "input"))
      (node (ref "H9") (pin "17") (pinfunction "17_17") (pintype "input"))
      (node (ref "J11") (pin "8") (pinfunction "8_8") (pintype "input"))
      (node (ref "J8") (pin "9") (pinfunction "9_9") (pintype "unspecified"))
    )
    (net (code "12") (name "A7") (class "Default")
      (node (ref "H4") (pin "9") (pinfunction "9_9") (pintype "input"))
      (node (ref "H9") (pin "19") (pinfunction "19_19") (pintype "input"))
      (node (ref "J11") (pin "10") (pinfunction "10_10") (pintype "input"))
      (node (ref "J8") (pin "10") (pinfunction "10_10") (pintype "unspecified"))
    )
    (net (code "13") (name "A8") (class "Default")
      (node (ref "H4") (pin "11") (pinfunction "11_11") (pintype "input"))
      (node (ref "J11") (pin "12") (pinfunction "12_12") (pintype "input"))
    )
    (net (code "14") (name "AGND") (class "Default")
      (node (ref "H4") (pin "3") (pinfunction "3_3") (pintype "input"))
      (node (ref "J11") (pin "4") (pinfunction "4_4") (pintype "input"))
    )
    (net (code "15") (name "AVDD") (class "Default")
      (node (ref "H1") (pin "6") (pinfunction "6_6") (pintype "input"))
      (node (ref "H4") (pin "1") (pinfunction "1_1") (pintype "input"))
      (node (ref "J1") (pin "5") (pinfunction "5_5") (pintype "unspecified"))
      (node (ref "J11") (pin "2") (pinfunction "2_2") (pintype "input"))
    )
    (net (code "16") (name "D2") (class "Default")
      (node (ref "D2") (pin "3") (pinfunction "3_3") (pintype "unspecified"))
      (node (ref "D2") (pin "4") (pinfunction "4_4") (pintype "unspecified"))
      (node (ref "H4") (pin "12") (pinfunction "12_12") (pintype "input"))
      (node (ref "J11") (pin "11") (pinfunction "11_11") (pintype "input"))
      (node (ref "U7") (pin "12") (pinfunction "PA5_12") (pintype "unspecified"))
    )
    (net (code "17") (name "D3") (class "Default")
      (node (ref "H4") (pin "10") (pinfunction "10_10") (pintype "input"))
      (node (ref "H7") (pin "3") (pinfunction "3_3") (pintype "unspecified"))
      (node (ref "J11") (pin "9") (pinfunction "9_9") (pintype "input"))
      (node (ref "U7") (pin "13") (pinfunction "PA6_13") (pintype "unspecified"))
    )
    (net (code "18") (name "D4") (class "Default")
      (node (ref "H4") (pin "8") (pinfunction "8_8") (pintype "input"))
      (node (ref "H7") (pin "5") (pinfunction "5_5") (pintype "unspecified"))
      (node (ref "H9") (pin "20") (pinfunction "20_20") (pintype "input"))
      (node (ref "J11") (pin "7") (pinfunction "7_7") (pintype "input"))
      (node (ref "J14") (pin "10") (pinfunction "10_10") (pintype "unspecified"))
      (node (ref "U7") (pin "14") (pinfunction "PA7_14") (pintype "unspecified"))
    )
    (net (code "19") (name "D5") (class "Default")
      (node (ref "H4") (pin "6") (pinfunction "6_6") (pintype "input"))
      (node (ref "H7") (pin "6") (pinfunction "6_6") (pintype "unspecified"))
      (node (ref "H9") (pin "18") (pinfunction "18_18") (pintype "input"))
      (node (ref "J11") (pin "5") (pinfunction "5_5") (pintype "input"))
      (node (ref "J14") (pin "9") (pinfunction "9_9") (pintype "unspecified"))
      (node (ref "U7") (pin "15") (pinfunction "PB0_15") (pintype "unspecified"))
    )
    (net (code "20") (name "D6") (class "Default")
      (node (ref "H4") (pin "4") (pinfunction "4_4") (pintype "input"))
      (node (ref "H7") (pin "4") (pinfunction "4_4") (pintype "unspecified"))
      (node (ref "J11") (pin "3") (pinfunction "3_3") (pintype "input"))
      (node (ref "R1") (pin "2") (pinfunction "2_2") (pintype "unspecified"))
      (node (ref "U1") (pin "4") (pinfunction "CLK_4") (pintype "unspecified"))
      (node (ref "U10") (pin "4") (pinfunction "CLK_4") (pintype "unspecified"))
      (node (ref "U7") (pin "16") (pinfunction "PB1_16") (pintype "unspecified"))
    )
    (net (code "21") (name "D7") (class "Default")
      (node (ref "H4") (pin "2") (pinfunction "2_2") (pintype "input"))
      (node (ref "J11") (pin "1") (pinfunction "1_1") (pintype "input"))
      (node (ref "R2") (pin "2") (pinfunction "2_2") (pintype "unspecified"))
      (node (ref "U7") (pin "17") (pinfunction "PB2_17") (pintype "unspecified"))
    )
    (net (code "22") (name "D8") (class "Default")
      (node (ref "H1") (pin "20") (pinfunction "20_20") (pintype "input"))
      (node (ref "H14") (pin "7") (pinfunction "7_7") (pintype "unspecified"))
      (node (ref "H6") (pin "8") (pinfunction "8_8") (pintype "unspecified"))
      (node (ref "H9") (pin "16") (pinfunction "16_16") (pintype "input"))
      (node (ref "J1") (pin "19") (pinfunction "19_19") (pintype "unspecified"))
      (node (ref "J14") (pin "8") (pinfunction "8_8") (pintype "unspecified"))
      (node (ref "U7") (pin "18") (pinfunction "PA8_18") (pintype "unspecified"))
    )
    (net (code "23") (name "D9") (class "Default")
      (node (ref "H1") (pin "18") (pinfunction "18_18") (pintype "input"))
      (node (ref "H14") (pin "6") (pinfunction "6_6") (pintype "unspecified"))
      (node (ref "H6") (pin "3") (pinfunction "3_3") (pintype "unspecified"))
      (node (ref "H9") (pin "14") (pinfunction "14_14") (pintype "input"))
      (node (ref "J1") (pin "17") (pinfunction "17_17") (pintype "unspecified"))
      (node (ref "J14") (pin "7") (pinfunction "7_7") (pintype "unspecified"))
      (node (ref "U7") (pin "20") (pinfunction "PC6_20") (pintype "unspecified"))
    )
    (net (code "24") (name "D10") (class "Default")
      (node (ref "H1") (pin "16") (pinfunction "16_16") (pintype "input"))
      (node (ref "H9") (pin "12") (pinfunction "12_12") (pintype "input"))
      (node (ref "J1") (pin "15") (pinfunction "15_15") (pintype "unspecified"))
      (node (ref "J14") (pin "6") (pinfunction "6_6") (pintype "unspecified"))
      (node (ref "J2") (pin "4") (pinfunction "4_4") (pintype "unspecified"))
    )
    (net (code "25") (name "D16") (class "Default")
      (node (ref "H1") (pin "1") (pinfunction "1_1") (pintype "input"))
      (node (ref "H10") (pin "3") (pinfunction "3_3") (pintype "unspecified"))
      (node (ref "H9") (pin "1") (pinfunction "1_1") (pintype "input"))
      (node (ref "J1") (pin "2") (pinfunction "2_2") (pintype "unspecified"))
      (node (ref "J8") (pin "1") (pinfunction "1_1") (pintype "unspecified"))
    )
    (net (code "26") (name "D17") (class "Default")
      (node (ref "H1") (pin "3") (pinfunction "3_3") (pintype "input"))
      (node (ref "H10") (pin "8") (pinfunction "8_8") (pintype "unspecified"))
      (node (ref "H9") (pin "3") (pinfunction "3_3") (pintype "input"))
      (node (ref "J1") (pin "4") (pinfunction "4_4") (pintype "unspecified"))
      (node (ref "J8") (pin "2") (pinfunction "2_2") (pintype "unspecified"))
    )
    (net (code "27") (name "D18") (class "Default")
      (node (ref "H1") (pin "5") (pinfunction "5_5") (pintype "input"))
      (node (ref "H9") (pin "5") (pinfunction "5_5") (pintype "input"))
      (node (ref "J1") (pin "6") (pinfunction "6_6") (pintype "unspecified"))
      (node (ref "J8") (pin "3") (pinfunction "3_3") (pintype "unspecified"))
      (node (ref "R10") (pin "1") (pinfunction "1_1") (pintype "unspecified"))
    )
    (net (code "28") (name "D19") (class "Default")
      (node (ref "H1") (pin "7") (pinfunction "7_7") (pintype "input"))
      (node (ref "H9") (pin "7") (pinfunction "7_7") (pintype "input"))
      (node (ref "J1") (pin "8") (pinfunction "8_8") (pintype "unspecified"))
      (node (ref "J8") (pin "4") (pinfunction "4_4") (pintype "unspecified"))
    )
    (net (code "29") (name "D21") (class "Default")
      (node (ref "H1") (pin "11") (pinfunction "11_11") (pintype "input"))
      (node (ref "J1") (pin "12") (pinfunction "12_12") (pintype "unspecified"))
    )
    (net (code "30") (name "D32") (class "Default")
      (node (ref "H4") (pin "29") (pinfunction "29_29") (pintype "input"))
      (node (ref "J11") (pin "30") (pinfunction "30_30") (pintype "input"))
    )
    (net (code "31") (name "D37") (class "Default")
      (node (ref "H4") (pin "30") (pinfunction "30_30") (pintype "input"))
      (node (ref "J11") (pin "29") (pinfunction "29_29") (pintype "input"))
      (node (ref "U7") (pin "25") (pinfunction "PA14-BOOT0_25") (pintype "unspecified"))
    )
    (net (code "32") (name "D38") (class "Default")
      (node (ref "H4") (pin "28") (pinfunction "28_28") (pintype "input"))
      (node (ref "J11") (pin "27") (pinfunction "27_27") (pintype "input"))
      (node (ref "U7") (pin "24") (pinfunction "PA13_24") (pintype "unspecified"))
    )
    (net (code "33") (name "D39") (class "Default")
      (node (ref "H4") (pin "26") (pinfunction "26_26") (pintype "input"))
      (node (ref "J11") (pin "25") (pinfunction "25_25") (pintype "input"))
    )
    (net (code "34") (name "D40") (class "Default")
      (node (ref "H4") (pin "24") (pinfunction "24_24") (pintype "input"))
      (node (ref "J11") (pin "23") (pinfunction "23_23") (pintype "input"))
    )
    (net (code "35") (name "D41") (class "Default")
      (node (ref "C17") (pin "1") (pinfunction "1_1") (pintype "unspecified"))
      (node (ref "H4") (pin "20") (pinfunction "20_20") (pintype "input"))
      (node (ref "J11") (pin "19") (pinfunction "19_19") (pintype "input"))
      (node (ref "R5") (pin "1") (pinfunction "1_1") (pintype "unspecified"))
      (node (ref "U1") (pin "1") (pinfunction "Data_1") (pintype "unspecified"))
      (node (ref "U10") (pin "1") (pinfunction "Data_1") (pintype "unspecified"))
      (node (ref "U2") (pin "2") (pinfunction "DQ_2") (pintype "unspecified"))
      (node (ref "U3") (pin "2") (pinfunction "DQ_2") (pintype "unspecified"))
    )
    (net (code "36") (name "D42") (class "Default")
      (node (ref "H4") (pin "18") (pinfunction "18_18") (pintype "input"))
      (node (ref "J11") (pin "17") (pinfunction "17_17") (pintype "input"))
    )
    (net (code "37") (name "D43") (class "Default")
      (node (ref "CARD2") (pin "7") (pinfunction "DAT0_7") (pintype "unspecified"))
      (node (ref "H2") (pin "2") (pinfunction "2_2") (pintype "input"))
      (node (ref "J3") (pin "1") (pinfunction "1_1") (pintype "input"))
    )
    (net (code "38") (name "D44") (class "Default")
      (node (ref "CARD2") (pin "8") (pinfunction "DAT1_8") (pintype "unspecified"))
      (node (ref "H2") (pin "4") (pinfunction "4_4") (pintype "input"))
      (node (ref "J3") (pin "3") (pinfunction "3_3") (pintype "input"))
    )
    (net (code "39") (name "D45") (class "Default")
      (node (ref "CARD2") (pin "1") (pinfunction "DAT2_1") (pintype "unspecified"))
      (node (ref "H2") (pin "6") (pinfunction "6_6") (pintype "input"))
      (node (ref "J3") (pin "5") (pinfunction "5_5") (pintype "input"))
    )
    (net (code "40") (name "D46") (class "Default")
      (node (ref "CARD2") (pin "2") (pinfunction "CD/DAT3_2") (pintype "unspecified"))
      (node (ref "H2") (pin "8") (pinfunction "8_8") (pintype "input"))
      (node (ref "J12") (pin "4") (pinfunction "4_4") (pintype "input"))
      (node (ref "J3") (pin "7") (pinfunction "7_7") (pintype "input"))
    )
    (net (code "41") (name "D47") (class "Default")
      (node (ref "CARD2") (pin "5") (pinfunction "CLX_5") (pintype "unspecified"))
      (node (ref "H2") (pin "10") (pinfunction "10_10") (pintype "input"))
      (node (ref "J3") (pin "9") (pinfunction "9_9") (pintype "input"))
    )
    (net (code "42") (name "D48") (class "Default")
      (node (ref "CARD2") (pin "3") (pinfunction "CMD_3") (pintype "unspecified"))
      (node (ref "H2") (pin "12") (pinfunction "12_12") (pintype "input"))
      (node (ref "J3") (pin "11") (pinfunction "11_11") (pintype "input"))
    )
    (net (code "43") (name "D49") (class "Default")
      (node (ref "H2") (pin "14") (pinfunction "14_14") (pintype "input"))
      (node (ref "J3") (pin "13") (pinfunction "13_13") (pintype "input"))
    )
    (net (code "44") (name "D50") (class "Default")
      (node (ref "H2") (pin "16") (pinfunction "16_16") (pintype "input"))
      (node (ref "J3") (pin "15") (pinfunction "15_15") (pintype "input"))
    )
    (net (code "45") (name "D51") (class "Default")
      (node (ref "H3") (pin "2") (pinfunction "2_2") (pintype "input"))
      (node (ref "J7") (pin "1") (pinfunction "1_1") (pintype "input"))
    )
    (net (code "46") (name "D52") (class "Default")
      (node (ref "H3") (pin "4") (pinfunction "4_4") (pintype "input"))
      (node (ref "J7") (pin "3") (pinfunction "3_3") (pintype "input"))
    )
    (net (code "47") (name "D53") (class "Default")
      (node (ref "H3") (pin "6") (pinfunction "6_6") (pintype "input"))
      (node (ref "J7") (pin "5") (pinfunction "5_5") (pintype "input"))
    )
    (net (code "48") (name "D54") (class "Default")
      (node (ref "H3") (pin "8") (pinfunction "8_8") (pintype "input"))
      (node (ref "J7") (pin "7") (pinfunction "7_7") (pintype "input"))
    )
    (net (code "49") (name "D55") (class "Default")
      (node (ref "H3") (pin "10") (pinfunction "10_10") (pintype "input"))
      (node (ref "J7") (pin "9") (pinfunction "9_9") (pintype "input"))
    )
    (net (code "50") (name "D56") (class "Default")
      (node (ref "H3") (pin "14") (pinfunction "14_14") (pintype "input"))
      (node (ref "J7") (pin "13") (pinfunction "13_13") (pintype "input"))
    )
    (net (code "51") (name "D57") (class "Default")
      (node (ref "H3") (pin "16") (pinfunction "16_16") (pintype "input"))
      (node (ref "J7") (pin "15") (pinfunction "15_15") (pintype "input"))
    )
    (net (code "52") (name "D71") (class "Default")
      (node (ref "H3") (pin "15") (pinfunction "15_15") (pintype "input"))
      (node (ref "J7") (pin "16") (pinfunction "16_16") (pintype "input"))
    )
    (net (code "53") (name "D72") (class "Default")
      (node (ref "H3") (pin "13") (pinfunction "13_13") (pintype "input"))
      (node (ref "J7") (pin "14") (pinfunction "14_14") (pintype "input"))
    )
    (net (code "54") (name "GND") (class "Default")
      (node (ref "A2") (pin "1") (pinfunction "1_1") (pintype "unspecified"))
      (node (ref "A2") (pin "2") (pinfunction "2_2") (pintype "unspecified"))
      (node (ref "C1") (pin "1") (pinfunction "1_1") (pintype "unspecified"))
      (node (ref "C10") (pin "2") (pinfunction "2_2") (pintype "unspecified"))
      (node (ref "C11") (pin "1") (pinfunction "1_1") (pintype "unspecified"))
      (node (ref "C12") (pin "1") (pinfunction "1_1") (pintype "unspecified"))
      (node (ref "C13") (pin "1") (pinfunction "1_1") (pintype "unspecified"))
      (node (ref "C15") (pin "1") (pinfunction "1_1") (pintype "unspecified"))
      (node (ref "C16") (pin "1") (pinfunction "1_1") (pintype "unspecified"))
      (node (ref "C18") (pin "1") (pinfunction "1_1") (pintype "unspecified"))
      (node (ref "C2") (pin "1") (pinfunction "1_1") (pintype "unspecified"))
      (node (ref "C3") (pin "1") (pinfunction "1_1") (pintype "unspecified"))
      (node (ref "C4") (pin "1") (pinfunction "1_1") (pintype "unspecified"))
      (node (ref "C5") (pin "1") (pinfunction "1_1") (pintype "unspecified"))
      (node (ref "C6") (pin "1") (pinfunction "1_1") (pintype "unspecified"))
      (node (ref "C7") (pin "1") (pinfunction "1_1") (pintype "unspecified"))
      (node (ref "CARD2") (pin "6") (pinfunction "VSS_6") (pintype "unspecified"))
      (node (ref "D2") (pin "1") (pinfunction "1_1") (pintype "unspecified"))
      (node (ref "D2") (pin "2") (pinfunction "2_2") (pintype "unspecified"))
      (node (ref "D6") (pin "2") (pinfunction "2_2") (pintype "unspecified"))
      (node (ref "D7") (pin "2") (pinfunction "2_2") (pintype "unspecified"))
      (node (ref "H1") (pin "8") (pinfunction "8_8") (pintype "input"))
      (node (ref "H10") (pin "1") (pinfunction "1_1") (pintype "unspecified"))
      (node (ref "H13") (pin "3") (pinfunction "3_3") (pintype "input"))
      (node (ref "H14") (pin "1") (pinfunction "1_1") (pintype "unspecified"))
      (node (ref "H2") (pin "11") (pinfunction "11_11") (pintype "input"))
      (node (ref "H2") (pin "13") (pinfunction "13_13") (pintype "input"))
      (node (ref "H3") (pin "12") (pinfunction "12_12") (pintype "input"))
      (node (ref "H4") (pin "17") (pinfunction "17_17") (pintype "input"))
      (node (ref "H4") (pin "22") (pinfunction "22_22") (pintype "input"))
      (node (ref "H4") (pin "27") (pinfunction "27_27") (pintype "input"))
      (node (ref "H4") (pin "5") (pinfunction "5_5") (pintype "input"))
      (node (ref "H5") (pin "1") (pinfunction "1_1") (pintype "unspecified"))
      (node (ref "H5") (pin "2") (pinfunction "2_2") (pintype "unspecified"))
      (node (ref "H5") (pin "3") (pinfunction "3_3") (pintype "unspecified"))
      (node (ref "H6") (pin "1") (pinfunction "1_1") (pintype "unspecified"))
      (node (ref "H7") (pin "2") (pinfunction "2_2") (pintype "unspecified"))
      (node (ref "J1") (pin "7") (pinfunction "7_7") (pintype "unspecified"))
      (node (ref "J10") (pin "2") (pinfunction "2_2") (pintype "unspecified"))
      (node (ref "J11") (pin "18") (pinfunction "18_18") (pintype "input"))
      (node (ref "J11") (pin "21") (pinfunction "21_21") (pintype "input"))
      (node (ref "J11") (pin "28") (pinfunction "28_28") (pintype "input"))
      (node (ref "J11") (pin "6") (pinfunction "6_6") (pintype "input"))
      (node (ref "J13") (pin "1") (pinfunction "1_1") (pintype "unspecified"))
      (node (ref "J15") (pin "2") (pinfunction "2_2") (pintype "input"))
      (node (ref "J17") (pin "1") (pinfunction "1_1") (pintype "unspecified"))
      (node (ref "J17") (pin "10") (pinfunction "10_10") (pintype "unspecified"))
      (node (ref "J17") (pin "2") (pinfunction "2_2") (pintype "unspecified"))
      (node (ref "J17") (pin "3") (pinfunction "3_3") (pintype "unspecified"))
      (node (ref "J17") (pin "4") (pinfunction "4_4") (pintype "unspecified"))
      (node (ref "J17") (pin "5") (pinfunction "5_5") (pintype "unspecified"))
      (node (ref "J17") (pin "6") (pinfunction "6_6") (pintype "unspecified"))
      (node (ref "J17") (pin "7") (pinfunction "7_7") (pintype "unspecified"))
      (node (ref "J17") (pin "8") (pinfunction "8_8") (pintype "unspecified"))
      (node (ref "J17") (pin "9") (pinfunction "9_9") (pintype "unspecified"))
      (node (ref "J3") (pin "12") (pinfunction "12_12") (pintype "input"))
      (node (ref "J3") (pin "14") (pinfunction "14_14") (pintype "input"))
      (node (ref "J4") (pin "1") (pinfunction "1_1") (pintype "unspecified"))
      (node (ref "J4") (pin "10") (pinfunction "10_10") (pintype "unspecified"))
      (node (ref "J4") (pin "2") (pinfunction "2_2") (pintype "unspecified"))
      (node (ref "J4") (pin "3") (pinfunction "3_3") (pintype "unspecified"))
      (node (ref "J4") (pin "4") (pinfunction "4_4") (pintype "unspecified"))
      (node (ref "J4") (pin "5") (pinfunction "5_5") (pintype "unspecified"))
      (node (ref "J4") (pin "6") (pinfunction "6_6") (pintype "unspecified"))
      (node (ref "J4") (pin "7") (pinfunction "7_7") (pintype "unspecified"))
      (node (ref "J4") (pin "8") (pinfunction "8_8") (pintype "unspecified"))
      (node (ref "J4") (pin "9") (pinfunction "9_9") (pintype "unspecified"))
      (node (ref "J7") (pin "11") (pinfunction "11_11") (pintype "input"))
      (node (ref "J9") (pin "1") (pinfunction "1_1") (pintype "unspecified"))
      (node (ref "J9") (pin "2") (pinfunction "2_2") (pintype "unspecified"))
      (node (ref "J9") (pin "3") (pinfunction "3_3") (pintype "unspecified"))
      (node (ref "MIC1") (pin "2") (pinfunction "GND_2") (pintype "unspecified"))
      (node (ref "MIC1") (pin "3") (pinfunction "GND_3") (pintype "unspecified"))
      (node (ref "NRST") (pin "1") (pinfunction "1_1") (pintype "unspecified"))
      (node (ref "NRST") (pin "2") (pinfunction "2_2") (pintype "unspecified"))
      (node (ref "NRST2") (pin "1") (pinfunction "1_1") (pintype "unspecified"))
      (node (ref "NRST2") (pin "2") (pinfunction "2_2") (pintype "unspecified"))
      (node (ref "R21") (pin "1") (pinfunction "1_1") (pintype "unspecified"))
      (node (ref "R23") (pin "2") (pinfunction "2_2") (pintype "unspecified"))
      (node (ref "SPK1") (pin "3") (pinfunction "3_3") (pintype "unspecified"))
      (node (ref "SPK1") (pin "4") (pinfunction "4_4") (pintype "unspecified"))
      (node (ref "U1") (pin "2") (pinfunction "L/R_2") (pintype "unspecified"))
      (node (ref "U1") (pin "3") (pinfunction "GND_3") (pintype "unspecified"))
      (node (ref "U10") (pin "3") (pinfunction "GND_3") (pintype "unspecified"))
      (node (ref "U15") (pin "1") (pinfunction "GND_1") (pintype "unspecified"))
      (node (ref "U2") (pin "1") (pinfunction "GND_1") (pintype "unspecified"))
      (node (ref "U3") (pin "1") (pinfunction "GND_1") (pintype "unspecified"))
      (node (ref "U4") (pin "2") (pinfunction "A1_2") (pintype "unspecified"))
      (node (ref "U4") (pin "3") (pinfunction "A2_3") (pintype "unspecified"))
      (node (ref "U4") (pin "4") (pinfunction "GND_4") (pintype "unspecified"))
      (node (ref "U4") (pin "7") (pinfunction "WP_7") (pintype "unspecified"))
      (node (ref "U5") (pin "4") (pinfunction "GND_4") (pintype "unspecified"))
      (node (ref "U6") (pin "4") (pinfunction "VEE/GND_4") (pintype "unspecified"))
      (node (ref "U7") (pin "5") (pinfunction "VSS/VSSA_5") (pintype "unspecified"))
      (node (ref "U8") (pin "7") (pinfunction "GND_7") (pintype "unspecified"))
      (node (ref "U9") (pin "4") (pinfunction "GND_4") (pintype "unspecified"))
      (node (ref "USB1") (pin "7") (pinfunction "EH_7") (pintype "unspecified"))
      (node (ref "USB1") (pin "A12") (pinfunction "GND_A12") (pintype "unspecified"))
      (node (ref "USB1") (pin "B12") (pinfunction "GND_B12") (pintype "unspecified"))
      (node (ref "X1") (pin "2") (pinfunction "GND_2") (pintype "unspecified"))
    )
    (net (code "55") (name "IOREF") (class "Default")
      (node (ref "H2") (pin "3") (pinfunction "3_3") (pintype "input"))
      (node (ref "J3") (pin "4") (pinfunction "4_4") (pintype "input"))
    )
    (net (code "56") (name "MISO") (class "Default")
      (node (ref "H1") (pin "12") (pinfunction "12_12") (pintype "input"))
      (node (ref "H6") (pin "7") (pinfunction "7_7") (pintype "unspecified"))
      (node (ref "H9") (pin "8") (pinfunction "8_8") (pintype "input"))
      (node (ref "J1") (pin "11") (pinfunction "11_11") (pintype "unspecified"))
      (node (ref "J14") (pin "4") (pinfunction "4_4") (pintype "unspecified"))
      (node (ref "U7") (pin "28") (pinfunction "PB4_28") (pintype "unspecified"))
    )
    (net (code "57") (name "MISO2") (class "Default")
      (node (ref "H1") (pin "19") (pinfunction "19_19") (pintype "input"))
      (node (ref "H10") (pin "7") (pinfunction "7_7") (pintype "unspecified"))
      (node (ref "H9") (pin "15") (pinfunction "15_15") (pintype "input"))
      (node (ref "J1") (pin "20") (pinfunction "20_20") (pintype "unspecified"))
      (node (ref "J8") (pin "8") (pinfunction "8_8") (pintype "unspecified"))
      (node (ref "U7") (pin "30") (pinfunction "PB6_30") (pintype "unspecified"))
    )
    (net (code "58") (name "MOSI") (class "Default")
      (node (ref "H1") (pin "14") (pinfunction "14_14") (pintype "input"))
      (node (ref "H14") (pin "4") (pinfunction "4_4") (pintype "unspecified"))
      (node (ref "H6") (pin "6") (pinfunction "6_6") (pintype "unspecified"))
      (node (ref "H9") (pin "10") (pinfunction "10_10") (pintype "input"))
      (node (ref "J1") (pin "13") (pinfunction "13_13") (pintype "unspecified"))
      (node (ref "J14") (pin "5") (pinfunction "5_5") (pintype "unspecified"))
      (node (ref "U7") (pin "29") (pinfunction "PB5_29") (pintype "unspecified"))
    )
    (net (code "59") (name "MOSI2") (class "Default")
      (node (ref "H1") (pin "13") (pinfunction "13_13") (pintype "input"))
      (node (ref "H10") (pin "6") (pinfunction "6_6") (pintype "unspecified"))
      (node (ref "H9") (pin "9") (pinfunction "9_9") (pintype "input"))
      (node (ref "J1") (pin "14") (pinfunction "14_14") (pintype "unspecified"))
      (node (ref "J8") (pin "5") (pinfunction "5_5") (pintype "unspecified"))
      (node (ref "U7") (pin "31") (pinfunction "PB7_31") (pintype "unspecified"))
    )
    (net (code "60") (name "NRST") (class "Default")
      (node (ref "H14") (pin "5") (pinfunction "5_5") (pintype "unspecified"))
      (node (ref "H2") (pin "5") (pinfunction "5_5") (pintype "input"))
      (node (ref "J3") (pin "6") (pinfunction "6_6") (pintype "input"))
      (node (ref "NRST") (pin "3") (pinfunction "3_3") (pintype "unspecified"))
      (node (ref "NRST") (pin "4") (pinfunction "4_4") (pintype "unspecified"))
    )
    (net (code "61") (name "NRST2") (class "Default")
      (node (ref "C7") (pin "2") (pinfunction "2_2") (pintype "unspecified"))
      (node (ref "J10") (pin "1") (pinfunction "1_1") (pintype "unspecified"))
      (node (ref "NRST2") (pin "3") (pinfunction "3_3") (pintype "unspecified"))
      (node (ref "NRST2") (pin "4") (pinfunction "4_4") (pintype "unspecified"))
      (node (ref "U7") (pin "6") (pinfunction "PF2-NRST_6") (pintype "unspecified"))
    )
    (net (code "62") (name "NSS") (class "Default")
      (node (ref "H1") (pin "9") (pinfunction "9_9") (pintype "input"))
      (node (ref "H6") (pin "4") (pinfunction "4_4") (pintype "unspecified"))
      (node (ref "J1") (pin "10") (pinfunction "10_10") (pintype "unspecified"))
      (node (ref "J2") (pin "3") (pinfunction "3_3") (pintype "unspecified"))
      (node (ref "U7") (pin "26") (pinfunction "PA15_26") (pintype "unspecified"))
    )
    (net (code "63") (name "NSS2") (class "Default")
      (node (ref "H1") (pin "17") (pinfunction "17_17") (pintype "input"))
      (node (ref "H10") (pin "4") (pinfunction "4_4") (pintype "unspecified"))
      (node (ref "H9") (pin "13") (pinfunction "13_13") (pintype "input"))
      (node (ref "J1") (pin "18") (pinfunction "18_18") (pintype "unspecified"))
      (node (ref "J2") (pin "1") (pinfunction "1_1") (pintype "unspecified"))
      (node (ref "J8") (pin "7") (pinfunction "7_7") (pintype "unspecified"))
      (node (ref "U7") (pin "1") (pinfunction "PB9_1") (pintype "unspecified"))
    )
    (net (code "64") (name "Net-(C8-Pad2)") (class "Default")
      (node (ref "C8") (pin "2") (pinfunction "2_2") (pintype "unspecified"))
      (node (ref "R18") (pin "1") (pinfunction "1_1") (pintype "unspecified"))
    )
    (net (code "65") (name "Net-(C9-Pad2)") (class "Default")
      (node (ref "C9") (pin "2") (pinfunction "2_2") (pintype "unspecified"))
      (node (ref "R7") (pin "1") (pinfunction "1_1") (pintype "unspecified"))
    )
    (net (code "66") (name "Net-(C11-Pad2)") (class "Default")
      (node (ref "C11") (pin "2") (pinfunction "2_2") (pintype "unspecified"))
      (node (ref "R10") (pin "2") (pinfunction "2_2") (pintype "unspecified"))
      (node (ref "R11") (pin "1") (pinfunction "1_1") (pintype "unspecified"))
    )
    (net (code "67") (name "Net-(C12-Pad2)") (class "Default")
      (node (ref "C12") (pin "2") (pinfunction "2_2") (pintype "unspecified"))
      (node (ref "H8") (pin "3") (pinfunction "3_3") (pintype "input"))
      (node (ref "R11") (pin "2") (pinfunction "2_2") (pintype "unspecified"))
    )
    (net (code "68") (name "Net-(D6-Pad1)") (class "Default")
      (node (ref "D6") (pin "1") (pinfunction "1_1") (pintype "unspecified"))
      (node (ref "R1") (pin "1") (pinfunction "1_1") (pintype "unspecified"))
    )
    (net (code "69") (name "Net-(D7-Pad1)") (class "Default")
      (node (ref "D7") (pin "1") (pinfunction "1_1") (pintype "unspecified"))
      (node (ref "R2") (pin "1") (pinfunction "1_1") (pintype "unspecified"))
    )
    (net (code "70") (name "Net-(U6-IN1+)") (class "Default")
      (node (ref "R20") (pin "2") (pinfunction "2_2") (pintype "unspecified"))
      (node (ref "R21") (pin "2") (pinfunction "2_2") (pintype "unspecified"))
      (node (ref "U6") (pin "3") (pinfunction "IN1+_3") (pintype "unspecified"))
    )
    (net (code "71") (name "Net-(U6-IN1-)") (class "Default")
      (node (ref "R18") (pin "2") (pinfunction "2_2") (pintype "unspecified"))
      (node (ref "R19") (pin "2") (pinfunction "2_2") (pintype "unspecified"))
      (node (ref "U6") (pin "2") (pinfunction "IN1-_2") (pintype "unspecified"))
    )
    (net (code "72") (name "Net-(U6-IN2+)") (class "Default")
      (node (ref "H13") (pin "2") (pinfunction "2_2") (pintype "input"))
      (node (ref "U6") (pin "5") (pinfunction "IN2+_5") (pintype "unspecified"))
    )
    (net (code "73") (name "Net-(U6-IN2-)") (class "Default")
      (node (ref "H13") (pin "1") (pinfunction "1_1") (pintype "input"))
      (node (ref "U6") (pin "6") (pinfunction "IN2-_6") (pintype "unspecified"))
      (node (ref "U6") (pin "7") (pinfunction "OUT2_7") (pintype "unspecified"))
    )
    (net (code "74") (name "Net-(U6-OUT1)") (class "Default")
      (node (ref "R19") (pin "1") (pinfunction "1_1") (pintype "unspecified"))
      (node (ref "R22") (pin "1") (pinfunction "1_1") (pintype "unspecified"))
      (node (ref "U6") (pin "1") (pinfunction "OUT1_1") (pintype "unspecified"))
    )
    (net (code "75") (name "Net-(U7-PC14-OSC32_IN)") (class "Default")
      (node (ref "U7") (pin "2") (pinfunction "PC14-OSC32_IN_2") (pintype "unspecified"))
      (node (ref "X1") (pin "3") (pinfunction "OUT_3") (pintype "unspecified"))
    )
    (net (code "76") (name "Net-(U8-+IN)") (class "Default")
      (node (ref "C10") (pin "1") (pinfunction "1_1") (pintype "unspecified"))
      (node (ref "U8") (pin "2") (pinfunction "Bypass_2") (pintype "unspecified"))
      (node (ref "U8") (pin "3") (pinfunction "+IN_3") (pintype "unspecified"))
    )
    (net (code "77") (name "Net-(U8--IN)") (class "Default")
      (node (ref "R7") (pin "2") (pinfunction "2_2") (pintype "unspecified"))
      (node (ref "R8") (pin "1") (pinfunction "1_1") (pintype "unspecified"))
      (node (ref "U8") (pin "4") (pinfunction "-IN_4") (pintype "unspecified"))
    )
    (net (code "78") (name "Net-(U8-SD)") (class "Default")
      (node (ref "J13") (pin "2") (pinfunction "2_2") (pintype "unspecified"))
      (node (ref "R9") (pin "1") (pinfunction "1_1") (pintype "unspecified"))
      (node (ref "U8") (pin "1") (pinfunction "SD_1") (pintype "unspecified"))
    )
    (net (code "79") (name "QCLK") (class "Default")
      (node (ref "H4") (pin "15") (pinfunction "15_15") (pintype "input"))
      (node (ref "J11") (pin "16") (pinfunction "16_16") (pintype "input"))
      (node (ref "U5") (pin "6") (pinfunction "CLK_6") (pintype "unspecified"))
      (node (ref "U9") (pin "6") (pinfunction "CLK_6") (pintype "unspecified"))
    )
    (net (code "80") (name "QCS") (class "Default")
      (node (ref "H4") (pin "13") (pinfunction "13_13") (pintype "input"))
      (node (ref "J11") (pin "14") (pinfunction "14_14") (pintype "input"))
      (node (ref "J12") (pin "2") (pinfunction "2_2") (pintype "input"))
    )
    (net (code "81") (name "QCS_F1") (class "Default")
      (node (ref "J12") (pin "1") (pinfunction "1_1") (pintype "input"))
      (node (ref "R3") (pin "1") (pinfunction "1_1") (pintype "unspecified"))
      (node (ref "U5") (pin "1") (pinfunction "CS#_1") (pintype "unspecified"))
    )
    (net (code "82") (name "QCS_F2") (class "Default")
      (node (ref "J12") (pin "3") (pinfunction "3_3") (pintype "input"))
      (node (ref "R4") (pin "1") (pinfunction "1_1") (pintype "unspecified"))
      (node (ref "U9") (pin "1") (pinfunction "CS#_1") (pintype "unspecified"))
    )
    (net (code "83") (name "QD0") (class "Default")
      (node (ref "H4") (pin "23") (pinfunction "23_23") (pintype "input"))
      (node (ref "J11") (pin "24") (pinfunction "24_24") (pintype "input"))
      (node (ref "J2") (pin "2") (pinfunction "2_2") (pintype "unspecified"))
      (node (ref "U5") (pin "5") (pinfunction "DI(IO0)_5") (pintype "unspecified"))
      (node (ref "U9") (pin "5") (pinfunction "DI(IO0)_5") (pintype "unspecified"))
    )
    (net (code "84") (name "QD1") (class "Default")
      (node (ref "H4") (pin "21") (pinfunction "21_21") (pintype "input"))
      (node (ref "J11") (pin "22") (pinfunction "22_22") (pintype "input"))
      (node (ref "U5") (pin "2") (pinfunction "DO(IO1)_2") (pintype "unspecified"))
      (node (ref "U9") (pin "2") (pinfunction "DO(IO1)_2") (pintype "unspecified"))
    )
    (net (code "85") (name "QD2") (class "Default")
      (node (ref "H4") (pin "25") (pinfunction "25_25") (pintype "input"))
      (node (ref "J11") (pin "26") (pinfunction "26_26") (pintype "input"))
      (node (ref "U5") (pin "3") (pinfunction "WP#(IO2)_3") (pintype "unspecified"))
      (node (ref "U9") (pin "3") (pinfunction "WP#(IO2)_3") (pintype "unspecified"))
    )
    (net (code "86") (name "QD3") (class "Default")
      (node (ref "H4") (pin "19") (pinfunction "19_19") (pintype "input"))
      (node (ref "J11") (pin "20") (pinfunction "20_20") (pintype "input"))
      (node (ref "U5") (pin "7") (pinfunction "HOLD#(IO3)_7") (pintype "unspecified"))
      (node (ref "U9") (pin "7") (pinfunction "HOLD#_or_RESET#(IO3)_7") (pintype "unspecified"))
    )
    (net (code "87") (name "SCK") (class "Default")
      (node (ref "H1") (pin "10") (pinfunction "10_10") (pintype "input"))
      (node (ref "H14") (pin "3") (pinfunction "3_3") (pintype "unspecified"))
      (node (ref "H6") (pin "5") (pinfunction "5_5") (pintype "unspecified"))
      (node (ref "H8") (pin "1") (pinfunction "1_1") (pintype "input"))
      (node (ref "H9") (pin "6") (pinfunction "6_6") (pintype "input"))
      (node (ref "J1") (pin "9") (pinfunction "9_9") (pintype "unspecified"))
      (node (ref "J14") (pin "3") (pinfunction "3_3") (pintype "unspecified"))
      (node (ref "U7") (pin "27") (pinfunction "PB3_27") (pintype "unspecified"))
    )
    (net (code "88") (name "SCK2") (class "Default")
      (node (ref "H1") (pin "15") (pinfunction "15_15") (pintype "input"))
      (node (ref "H10") (pin "5") (pinfunction "5_5") (pintype "unspecified"))
      (node (ref "H9") (pin "11") (pinfunction "11_11") (pintype "input"))
      (node (ref "J1") (pin "16") (pinfunction "16_16") (pintype "unspecified"))
      (node (ref "J8") (pin "6") (pinfunction "6_6") (pintype "unspecified"))
      (node (ref "U7") (pin "32") (pinfunction "PB8_32") (pintype "unspecified"))
    )
    (net (code "89") (name "SCL") (class "Default")
      (node (ref "H1") (pin "2") (pinfunction "2_2") (pintype "input"))
      (node (ref "H9") (pin "2") (pinfunction "2_2") (pintype "input"))
      (node (ref "J1") (pin "1") (pinfunction "1_1") (pintype "unspecified"))
      (node (ref "J14") (pin "1") (pinfunction "1_1") (pintype "unspecified"))
      (node (ref "R6") (pin "1") (pinfunction "1_1") (pintype "unspecified"))
      (node (ref "U4") (pin "6") (pinfunction "SCL_6") (pintype "unspecified"))
      (node (ref "U7") (pin "22") (pinfunction "PA11[PA9]_22") (pintype "unspecified"))
    )
    (net (code "90") (name "SDA") (class "Default")
      (node (ref "H1") (pin "4") (pinfunction "4_4") (pintype "input"))
      (node (ref "H9") (pin "4") (pinfunction "4_4") (pintype "input"))
      (node (ref "J1") (pin "3") (pinfunction "3_3") (pintype "unspecified"))
      (node (ref "J14") (pin "2") (pinfunction "2_2") (pintype "unspecified"))
      (node (ref "R17") (pin "1") (pinfunction "1_1") (pintype "unspecified"))
      (node (ref "U4") (pin "5") (pinfunction "SDA_5") (pintype "unspecified"))
      (node (ref "U7") (pin "23") (pinfunction "PA12[PA10]_23") (pintype "unspecified"))
    )
    (net (code "91") (name "SPK2") (class "Default")
      (node (ref "C9") (pin "1") (pinfunction "1_1") (pintype "unspecified"))
      (node (ref "H8") (pin "2") (pinfunction "2_2") (pintype "input"))
    )
    (net (code "92") (name "URX") (class "Default")
      (node (ref "H4") (pin "16") (pinfunction "16_16") (pintype "input"))
      (node (ref "H7") (pin "1") (pinfunction "1_1") (pintype "unspecified"))
      (node (ref "J11") (pin "15") (pinfunction "15_15") (pintype "input"))
      (node (ref "U7") (pin "19") (pinfunction "PA9_19") (pintype "unspecified"))
    )
    (net (code "93") (name "UTX") (class "Default")
      (node (ref "H4") (pin "14") (pinfunction "14_14") (pintype "input"))
      (node (ref "H7") (pin "8") (pinfunction "8_8") (pintype "unspecified"))
      (node (ref "J11") (pin "13") (pinfunction "13_13") (pintype "input"))
      (node (ref "U7") (pin "21") (pinfunction "PA10_21") (pintype "unspecified"))
    )
    (net (code "94") (name "VIN") (class "Default")
      (node (ref "H2") (pin "15") (pinfunction "15_15") (pintype "input"))
      (node (ref "J3") (pin "16") (pinfunction "16_16") (pintype "input"))
    )
    (net (code "95") (name "VO1") (class "Default")
      (node (ref "J15") (pin "3") (pinfunction "3_3") (pintype "input"))
      (node (ref "R8") (pin "2") (pinfunction "2_2") (pintype "unspecified"))
      (node (ref "SPK1") (pin "2") (pinfunction "-_2") (pintype "unspecified"))
      (node (ref "U8") (pin "5") (pinfunction "VO1_5") (pintype "unspecified"))
    )
    (net (code "96") (name "VO2") (class "Default")
      (node (ref "J15") (pin "1") (pinfunction "1_1") (pintype "input"))
      (node (ref "SPK1") (pin "1") (pinfunction "+_1") (pintype "unspecified"))
      (node (ref "U8") (pin "8") (pinfunction "VO2_8") (pintype "unspecified"))
    )
    (net (code "97") (name "unconnected-(CARD2-CD-Pad9)") (class "Default")
      (node (ref "CARD2") (pin "9") (pinfunction "CD_9") (pintype "unspecified+no_connect"))
    )
    (net (code "98") (name "unconnected-(CARD2-SHELL-Pad10)") (class "Default")
      (node (ref "CARD2") (pin "10") (pinfunction "SHELL_10") (pintype "unspecified+no_connect"))
    )
    (net (code "99") (name "unconnected-(CARD2-SHELL-Pad11)") (class "Default")
      (node (ref "CARD2") (pin "11") (pinfunction "SHELL_11") (pintype "unspecified+no_connect"))
    )
    (net (code "100") (name "unconnected-(CARD2-SHELL-Pad12)") (class "Default")
      (node (ref "CARD2") (pin "12") (pinfunction "SHELL_12") (pintype "unspecified+no_connect"))
    )
    (net (code "101") (name "unconnected-(CARD2-SHELL-Pad13)") (class "Default")
      (node (ref "CARD2") (pin "13") (pinfunction "SHELL_13") (pintype "unspecified+no_connect"))
    )
    (net (code "102") (name "unconnected-(H2-Pad1)") (class "Default")
      (node (ref "H2") (pin "1") (pinfunction "1_1") (pintype "input"))
    )
    (net (code "103") (name "unconnected-(H14-Pad8)") (class "Default")
      (node (ref "H14") (pin "8") (pinfunction "8_8") (pintype "unspecified"))
    )
    (net (code "104") (name "unconnected-(J3-Pad2)") (class "Default")
      (node (ref "J3") (pin "2") (pinfunction "2_2") (pintype "input"))
    )
    (net (code "105") (name "unconnected-(U7-PC15-OSC32_OUT-Pad3)") (class "Default")
      (node (ref "U7") (pin "3") (pinfunction "PC15-OSC32_OUT_3") (pintype "unspecified"))
    )
    (net (code "106") (name "unconnected-(U15-VOUT-Pad4)") (class "Default")
      (node (ref "U15") (pin "4") (pinfunction "VOUT_4") (pintype "unspecified"))
    )
    (net (code "107") (name "unconnected-(USB1-CC1-PadA5)") (class "Default")
      (node (ref "USB1") (pin "A5") (pinfunction "CC1_A5") (pintype "unspecified"))
    )
    (net (code "108") (name "unconnected-(USB1-CC2-PadB5)") (class "Default")
      (node (ref "USB1") (pin "B5") (pinfunction "CC2_B5") (pintype "unspecified"))
    )
    (net (code "109") (name "unconnected-(X1-OE-Pad1)") (class "Default")
      (node (ref "X1") (pin "1") (pinfunction "OE_1") (pintype "unspecified"))
    )
  )
)
